# input-output_iCESDuck-ShieldControler.net
KiCad netlist of a schematic drawn in EasyEDA
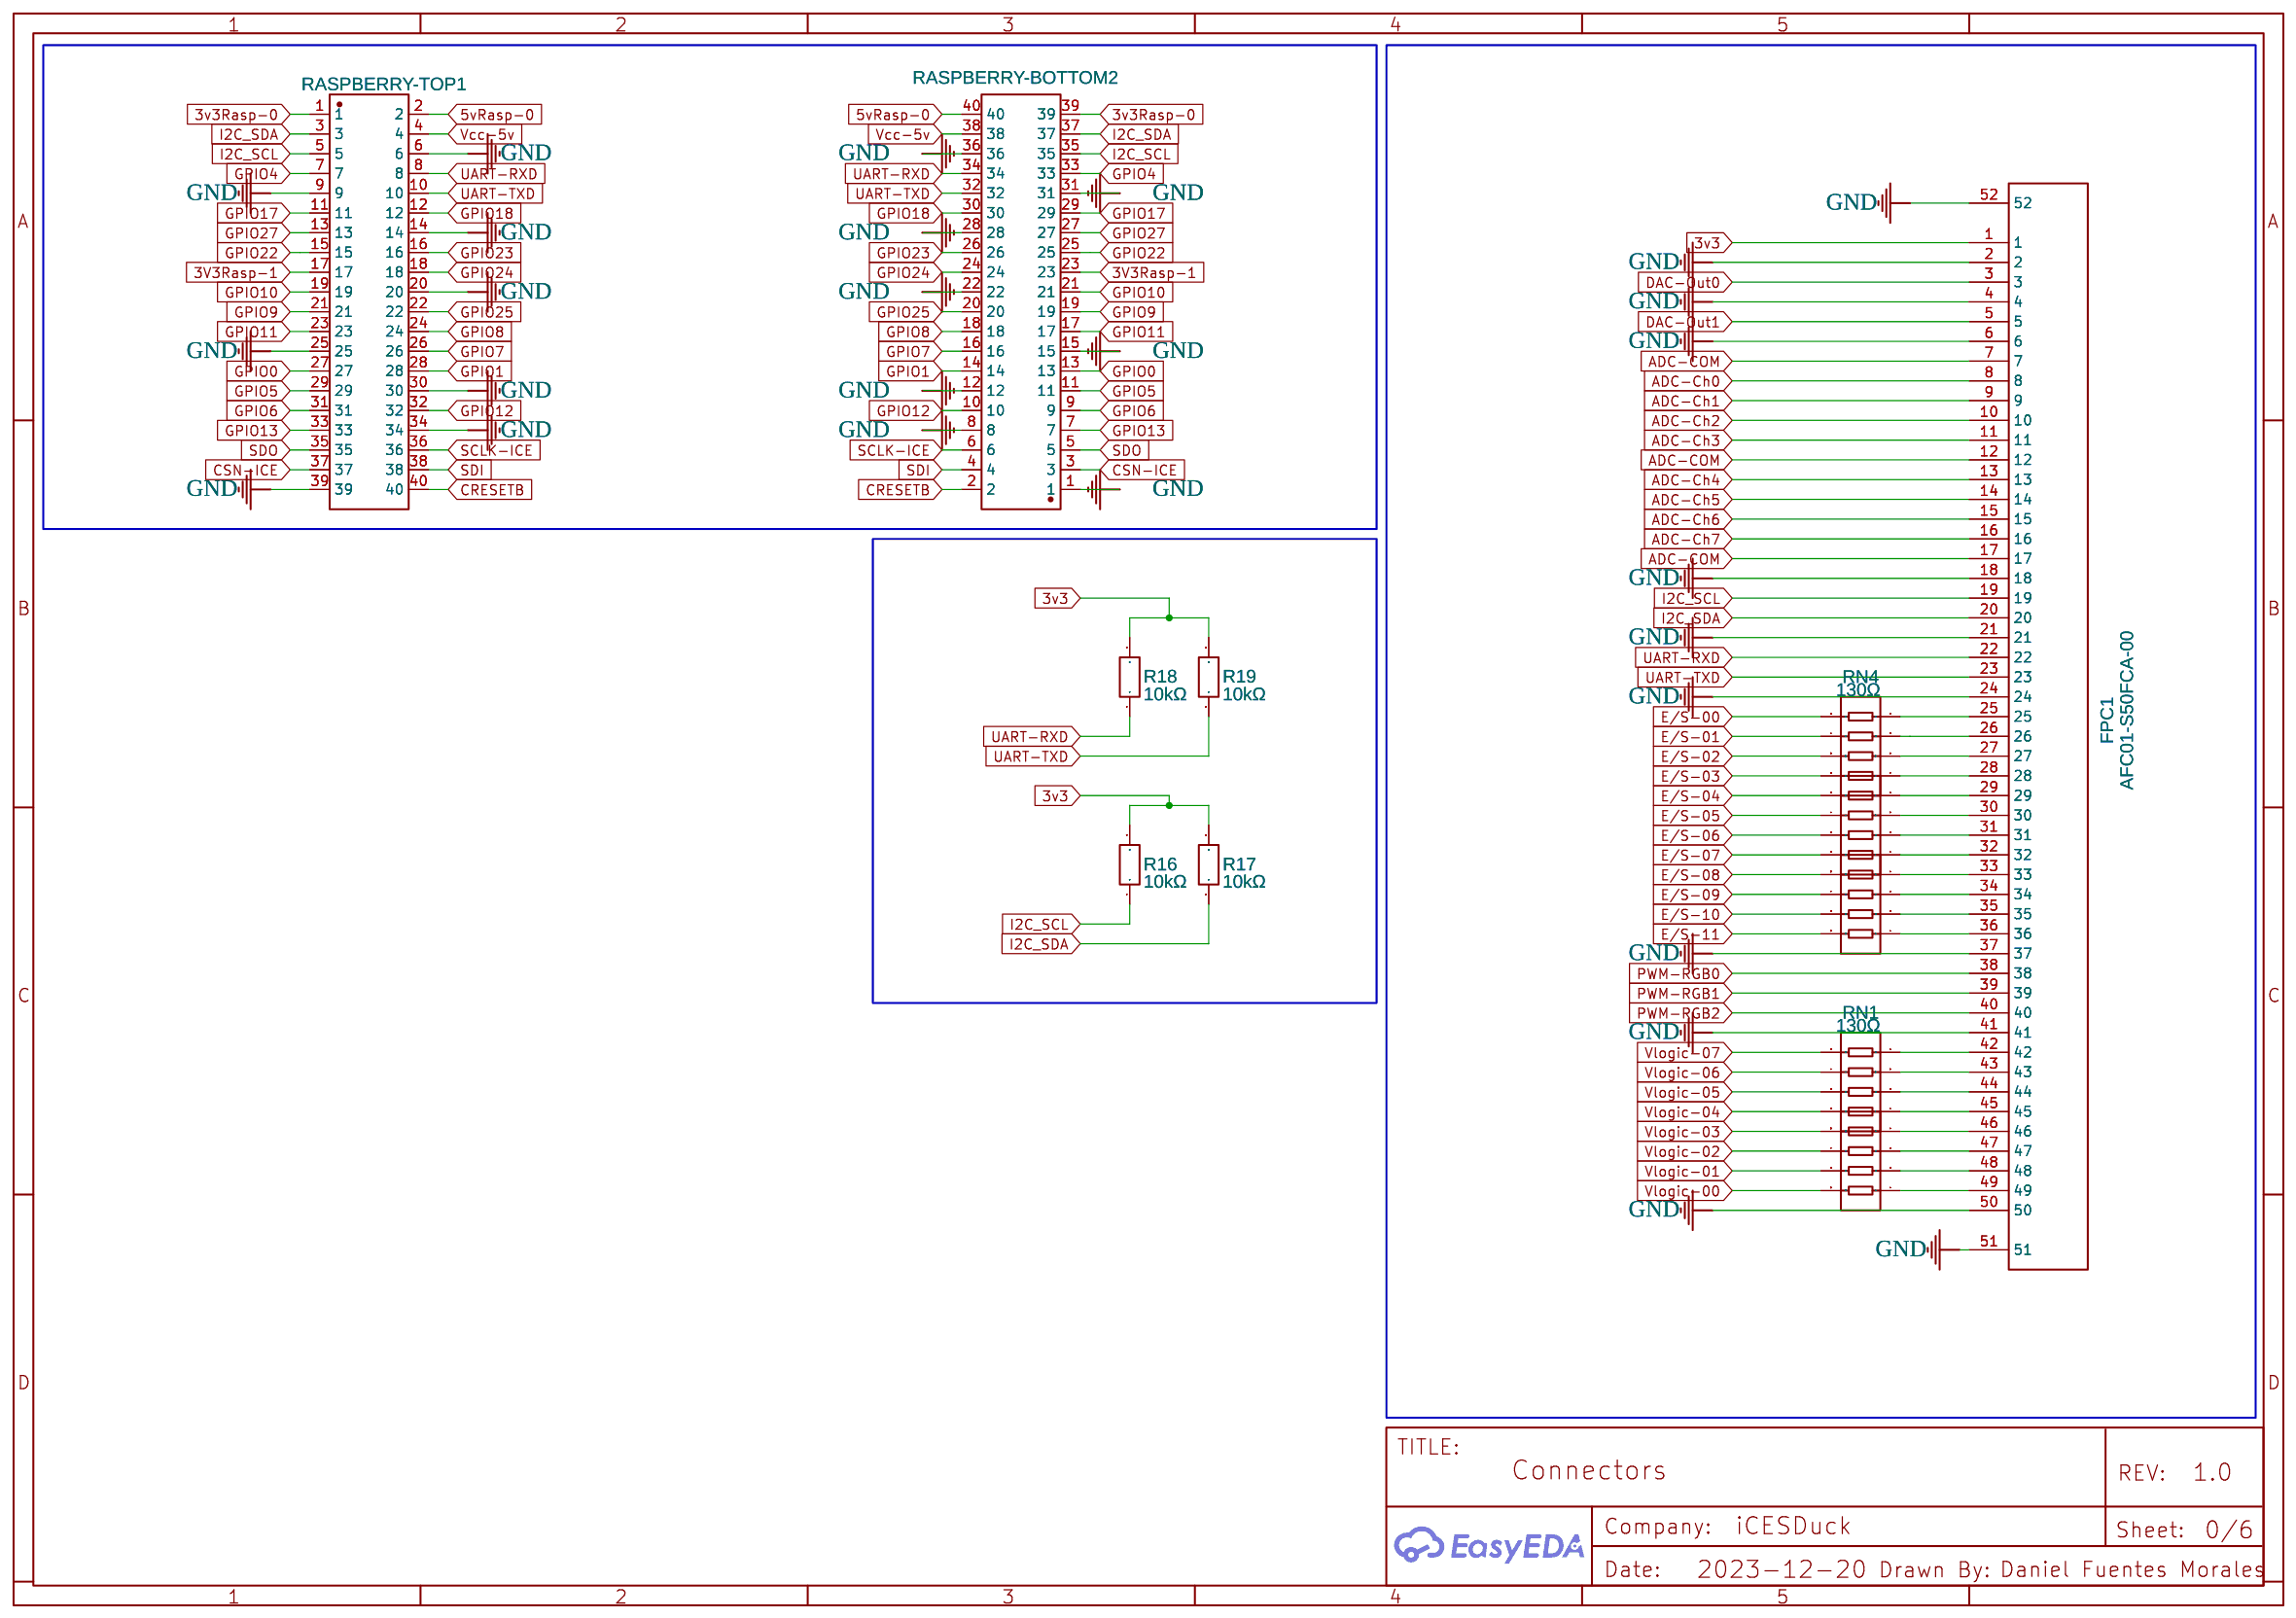
[diagram p0: Connectors]
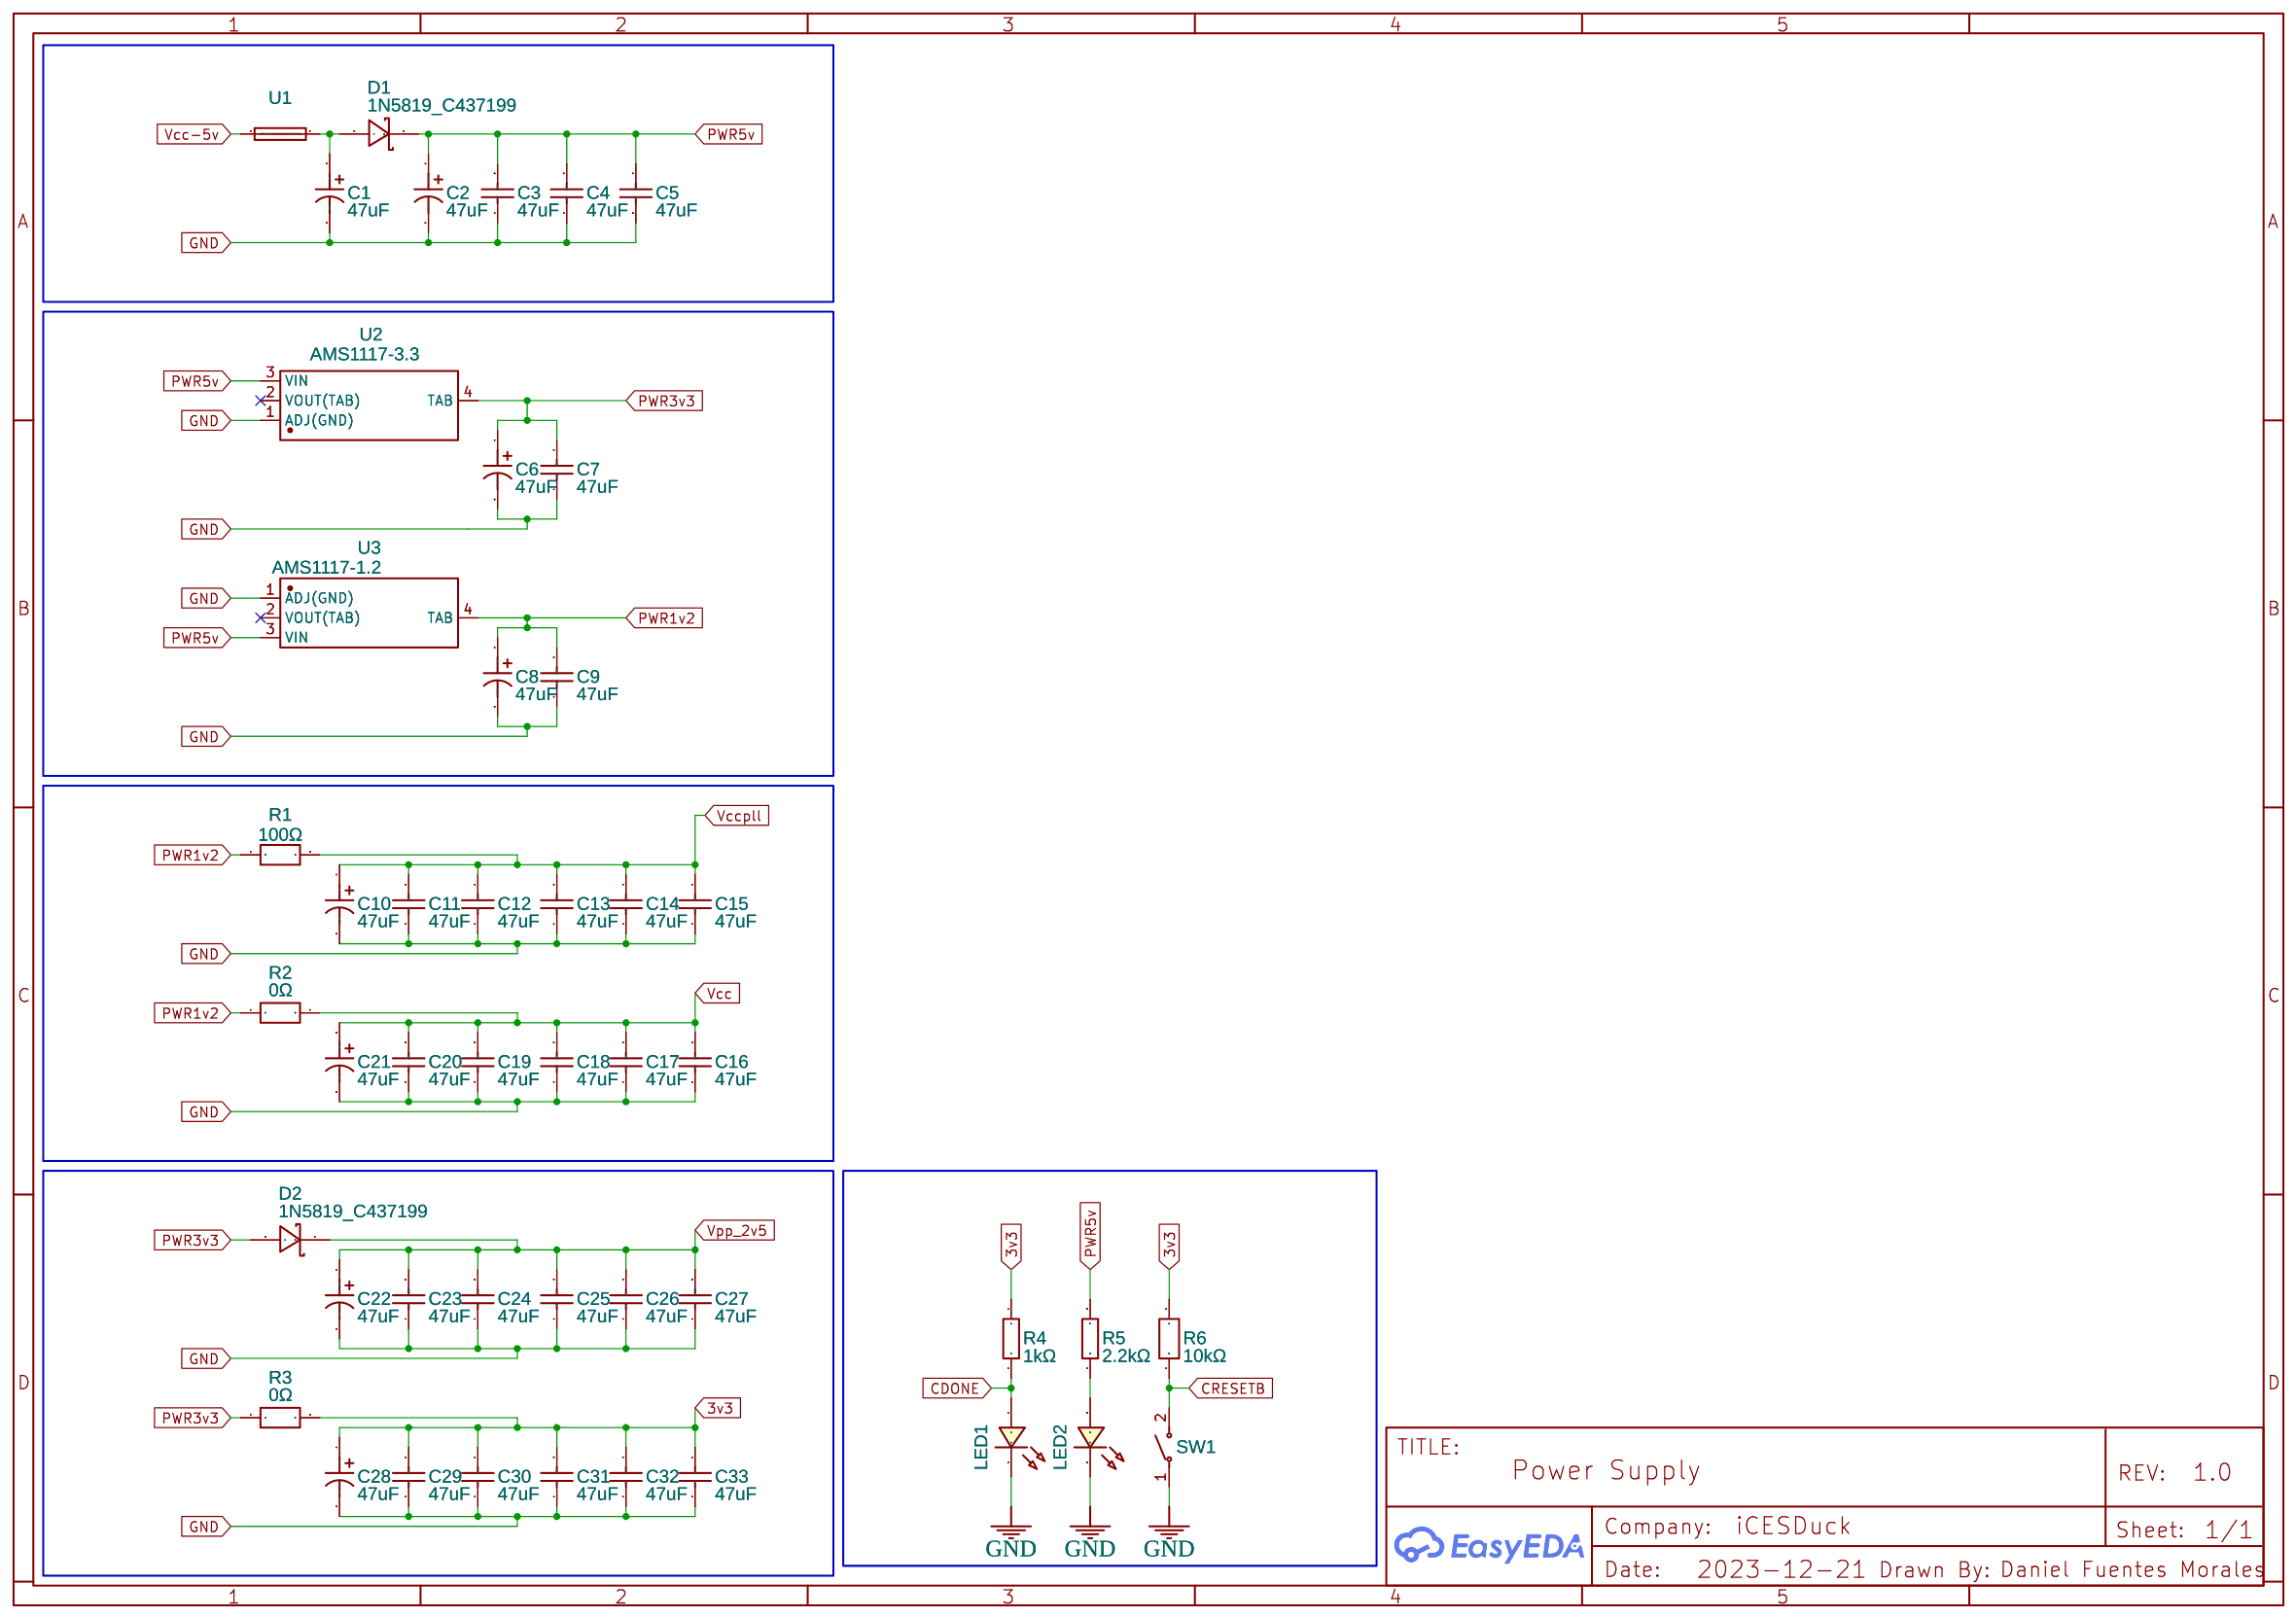
[diagram p1: power supply]
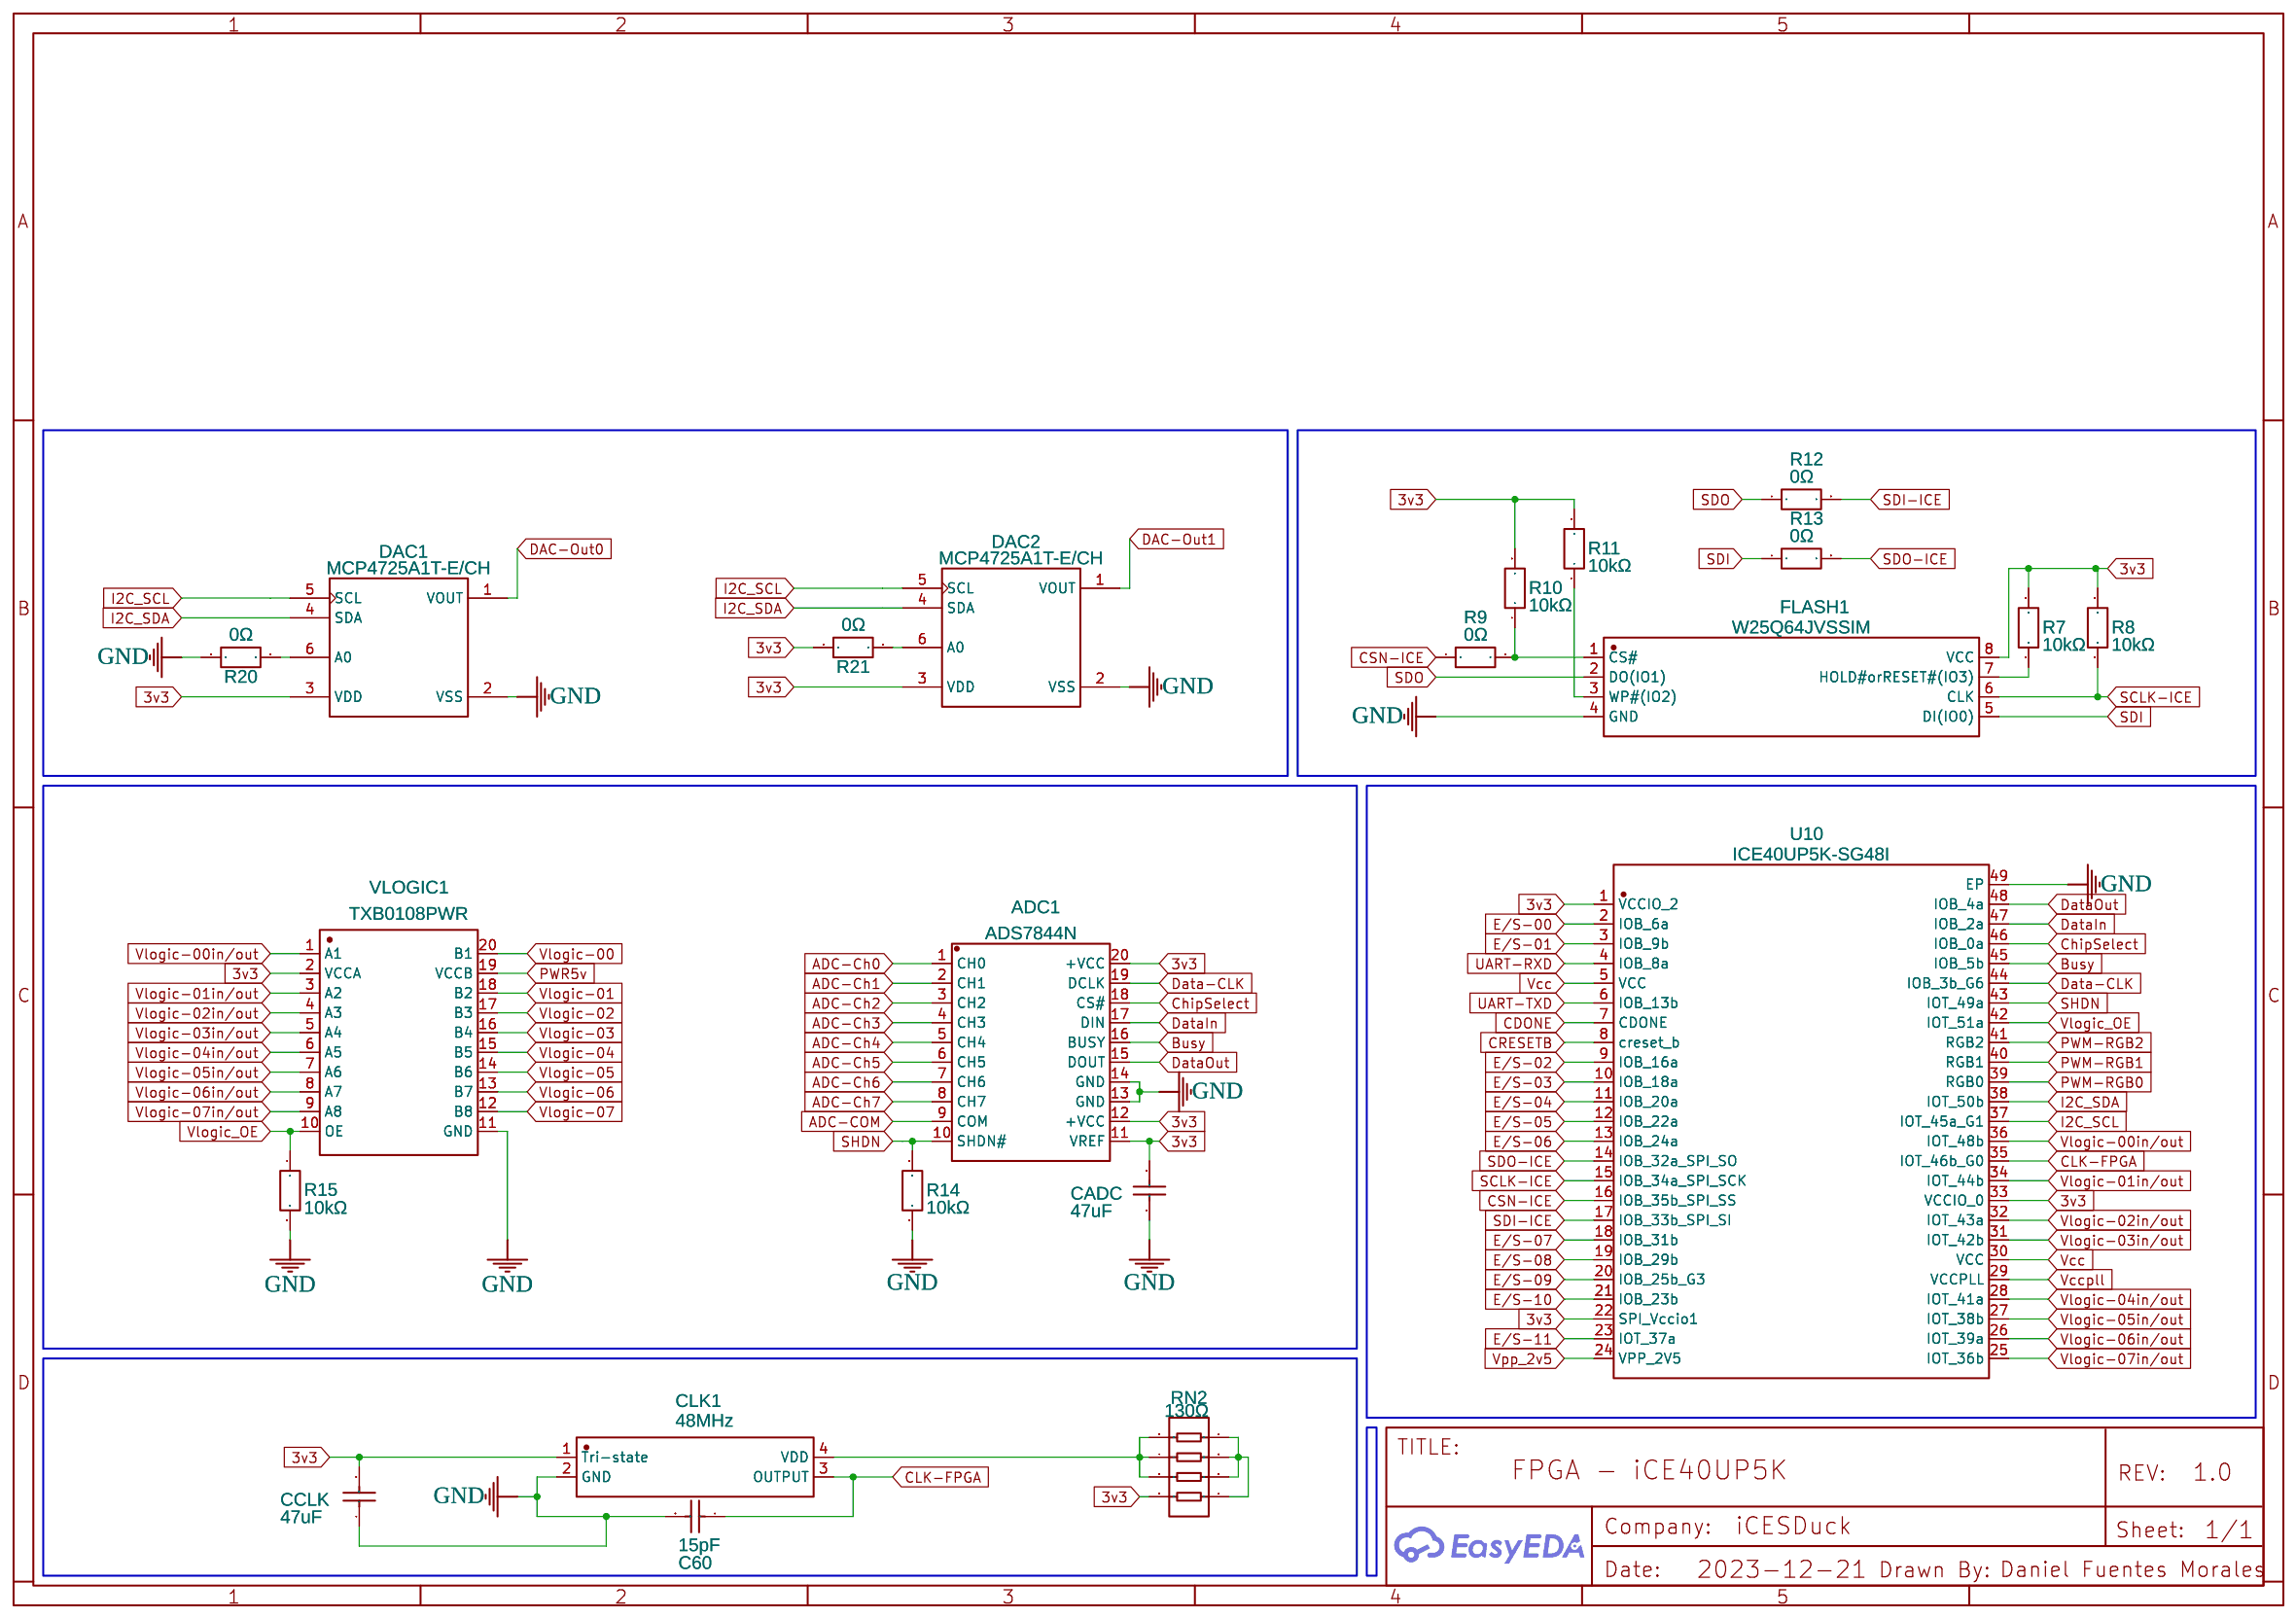
[diagram p2: FPGA - iCE40UP5k]

(export (version "E")
  (design (tool "Eeschema 10.0.6"))
  (components
    (comp (ref "FPC1")
      (value "AFC01-S50FCA-00")
      (fields (field (name "Manufacturer") "JS(钜硕电子)"))
      (libsource (lib "") (part "AFC01-S50FCA-00"))
    )
    (comp (ref "R16")
      (value "10kΩ")
      (fields (field (name "Manufacturer Part") "FRP1206J103 TS") (field (name "Manufacturer") "FOJAN(富捷)"))
      (libsource (lib "") (part "FRP1206J103 TS"))
    )
    (comp (ref "R17")
      (value "10kΩ")
      (fields (field (name "Manufacturer Part") "FRP1206J103 TS") (field (name "Manufacturer") "FOJAN(富捷)"))
      (libsource (lib "") (part "FRP1206J103 TS"))
    )
    (comp (ref "R18")
      (value "10kΩ")
      (fields (field (name "Manufacturer Part") "FRP1206J103 TS") (field (name "Manufacturer") "FOJAN(富捷)"))
      (libsource (lib "") (part "FRP1206J103 TS"))
    )
    (comp (ref "R19")
      (value "10kΩ")
      (fields (field (name "Manufacturer Part") "FRP1206J103 TS") (field (name "Manufacturer") "FOJAN(富捷)"))
      (libsource (lib "") (part "FRP1206J103 TS"))
    )
    (comp (ref "RASPBERRY-BOTTOM2")
      (value "FH-00148")
      (fields (field (name "Manufacturer") "Liansheng(连盛)"))
      (libsource (lib "") (part "FH-00148"))
    )
    (comp (ref "RASPBERRY-TOP1")
      (value "FH-00148")
      (fields (field (name "Manufacturer") "Liansheng(连盛)"))
      (libsource (lib "") (part "FH-00148_1"))
    )
    (comp (ref "RN1")
      (value "130Ω")
      (fields
        (field (name "Manufacturer Part") "4D03WGJ0131T5E")
        (field (name "Manufacturer") "UNI-ROYAL(厚声)")
      )
      (libsource (lib "") (part "4D03WGJ0131T5E"))
    )
    (comp (ref "RN3")
      (value "130Ω")
      (fields
        (field (name "Manufacturer Part") "4D03WGJ0131T5E")
        (field (name "Manufacturer") "UNI-ROYAL(厚声)")
      )
      (libsource (lib "") (part "4D03WGJ0131T5E"))
    )
    (comp (ref "RN4")
      (value "130Ω")
      (fields
        (field (name "Manufacturer Part") "4D03WGJ0131T5E")
        (field (name "Manufacturer") "UNI-ROYAL(厚声)")
      )
      (libsource (lib "") (part "4D03WGJ0131T5E"))
    )
    (comp (ref "RN5")
      (value "130Ω")
      (fields
        (field (name "Manufacturer Part") "4D03WGJ0131T5E")
        (field (name "Manufacturer") "UNI-ROYAL(厚声)")
      )
      (libsource (lib "") (part "4D03WGJ0131T5E"))
    )
    (comp (ref "RN6")
      (value "130Ω")
      (fields
        (field (name "Manufacturer Part") "4D03WGJ0131T5E")
        (field (name "Manufacturer") "UNI-ROYAL(厚声)")
      )
      (libsource (lib "") (part "4D03WGJ0131T5E"))
    )
    (comp (ref "C1")
      (value "47uF")
      (fields
        (field (name "Manufacturer Part") "CA45-A-10V-47uF-M")
        (field (name "Manufacturer") "CEC(振华新云)")
      )
      (libsource (lib "") (part "CA45-A-10V-47UF-M"))
    )
    (comp (ref "C2")
      (value "47uF")
      (fields
        (field (name "Manufacturer Part") "CA45-A-10V-47uF-M")
        (field (name "Manufacturer") "CEC(振华新云)")
      )
      (libsource (lib "") (part "CA45-A-10V-47UF-M"))
    )
    (comp (ref "C3")
      (value "47uF")
      (fields (field (name "Manufacturer Part") "C2012X5R1A476MTJ00E") (field (name "Manufacturer") "TDK"))
      (libsource (lib "") (part "C2012X5R1A476MTJ00E"))
    )
    (comp (ref "C4")
      (value "47uF")
      (fields (field (name "Manufacturer Part") "C2012X5R1A476MTJ00E") (field (name "Manufacturer") "TDK"))
      (libsource (lib "") (part "C2012X5R1A476MTJ00E"))
    )
    (comp (ref "C5")
      (value "47uF")
      (fields (field (name "Manufacturer Part") "C2012X5R1A476MTJ00E") (field (name "Manufacturer") "TDK"))
      (libsource (lib "") (part "C2012X5R1A476MTJ00E"))
    )
    (comp (ref "C6")
      (value "47uF")
      (fields
        (field (name "Manufacturer Part") "CA45-A-10V-47uF-M")
        (field (name "Manufacturer") "CEC(振华新云)")
      )
      (libsource (lib "") (part "CA45-A-10V-47UF-M"))
    )
    (comp (ref "C7")
      (value "47uF")
      (fields (field (name "Manufacturer Part") "C2012X5R1A476MTJ00E") (field (name "Manufacturer") "TDK"))
      (libsource (lib "") (part "C2012X5R1A476MTJ00E"))
    )
    (comp (ref "C8")
      (value "47uF")
      (fields
        (field (name "Manufacturer Part") "CA45-A-10V-47uF-M")
        (field (name "Manufacturer") "CEC(振华新云)")
      )
      (libsource (lib "") (part "CA45-A-10V-47UF-M"))
    )
    (comp (ref "C9")
      (value "47uF")
      (fields (field (name "Manufacturer Part") "C2012X5R1A476MTJ00E") (field (name "Manufacturer") "TDK"))
      (libsource (lib "") (part "C2012X5R1A476MTJ00E"))
    )
    (comp (ref "C10")
      (value "47uF")
      (fields
        (field (name "Manufacturer Part") "CA45-A-10V-47uF-M")
        (field (name "Manufacturer") "CEC(振华新云)")
      )
      (libsource (lib "") (part "CA45-A-10V-47UF-M"))
    )
    (comp (ref "C11")
      (value "47uF")
      (fields (field (name "Manufacturer Part") "C2012X5R1A476MTJ00E") (field (name "Manufacturer") "TDK"))
      (libsource (lib "") (part "C2012X5R1A476MTJ00E"))
    )
    (comp (ref "C12")
      (value "47uF")
      (fields (field (name "Manufacturer Part") "C2012X5R1A476MTJ00E") (field (name "Manufacturer") "TDK"))
      (libsource (lib "") (part "C2012X5R1A476MTJ00E"))
    )
    (comp (ref "C13")
      (value "47uF")
      (fields (field (name "Manufacturer Part") "C2012X5R1A476MTJ00E") (field (name "Manufacturer") "TDK"))
      (libsource (lib "") (part "C2012X5R1A476MTJ00E"))
    )
    (comp (ref "C14")
      (value "47uF")
      (fields (field (name "Manufacturer Part") "C2012X5R1A476MTJ00E") (field (name "Manufacturer") "TDK"))
      (libsource (lib "") (part "C2012X5R1A476MTJ00E"))
    )
    (comp (ref "C15")
      (value "47uF")
      (fields (field (name "Manufacturer Part") "C2012X5R1A476MTJ00E") (field (name "Manufacturer") "TDK"))
      (libsource (lib "") (part "C2012X5R1A476MTJ00E"))
    )
    (comp (ref "C16")
      (value "47uF")
      (fields (field (name "Manufacturer Part") "C2012X5R1A476MTJ00E") (field (name "Manufacturer") "TDK"))
      (libsource (lib "") (part "C2012X5R1A476MTJ00E"))
    )
    (comp (ref "C17")
      (value "47uF")
      (fields (field (name "Manufacturer Part") "C2012X5R1A476MTJ00E") (field (name "Manufacturer") "TDK"))
      (libsource (lib "") (part "C2012X5R1A476MTJ00E"))
    )
    (comp (ref "C18")
      (value "47uF")
      (fields (field (name "Manufacturer Part") "C2012X5R1A476MTJ00E") (field (name "Manufacturer") "TDK"))
      (libsource (lib "") (part "C2012X5R1A476MTJ00E"))
    )
    (comp (ref "C19")
      (value "47uF")
      (fields (field (name "Manufacturer Part") "C2012X5R1A476MTJ00E") (field (name "Manufacturer") "TDK"))
      (libsource (lib "") (part "C2012X5R1A476MTJ00E"))
    )
    (comp (ref "C20")
      (value "47uF")
      (fields (field (name "Manufacturer Part") "C2012X5R1A476MTJ00E") (field (name "Manufacturer") "TDK"))
      (libsource (lib "") (part "C2012X5R1A476MTJ00E"))
    )
    (comp (ref "C21")
      (value "47uF")
      (fields
        (field (name "Manufacturer Part") "CA45-A-10V-47uF-M")
        (field (name "Manufacturer") "CEC(振华新云)")
      )
      (libsource (lib "") (part "CA45-A-10V-47UF-M"))
    )
    (comp (ref "C22")
      (value "47uF")
      (fields
        (field (name "Manufacturer Part") "CA45-A-10V-47uF-M")
        (field (name "Manufacturer") "CEC(振华新云)")
      )
      (libsource (lib "") (part "CA45-A-10V-47UF-M"))
    )
    (comp (ref "C23")
      (value "47uF")
      (fields (field (name "Manufacturer Part") "C2012X5R1A476MTJ00E") (field (name "Manufacturer") "TDK"))
      (libsource (lib "") (part "C2012X5R1A476MTJ00E"))
    )
    (comp (ref "C24")
      (value "47uF")
      (fields (field (name "Manufacturer Part") "C2012X5R1A476MTJ00E") (field (name "Manufacturer") "TDK"))
      (libsource (lib "") (part "C2012X5R1A476MTJ00E"))
    )
    (comp (ref "C25")
      (value "47uF")
      (fields (field (name "Manufacturer Part") "C2012X5R1A476MTJ00E") (field (name "Manufacturer") "TDK"))
      (libsource (lib "") (part "C2012X5R1A476MTJ00E"))
    )
    (comp (ref "C26")
      (value "47uF")
      (fields (field (name "Manufacturer Part") "C2012X5R1A476MTJ00E") (field (name "Manufacturer") "TDK"))
      (libsource (lib "") (part "C2012X5R1A476MTJ00E"))
    )
    (comp (ref "C27")
      (value "47uF")
      (fields (field (name "Manufacturer Part") "C2012X5R1A476MTJ00E") (field (name "Manufacturer") "TDK"))
      (libsource (lib "") (part "C2012X5R1A476MTJ00E"))
    )
    (comp (ref "C28")
      (value "47uF")
      (fields
        (field (name "Manufacturer Part") "CA45-A-10V-47uF-M")
        (field (name "Manufacturer") "CEC(振华新云)")
      )
      (libsource (lib "") (part "CA45-A-10V-47UF-M"))
    )
    (comp (ref "C29")
      (value "47uF")
      (fields (field (name "Manufacturer Part") "C2012X5R1A476MTJ00E") (field (name "Manufacturer") "TDK"))
      (libsource (lib "") (part "C2012X5R1A476MTJ00E"))
    )
    (comp (ref "C30")
      (value "47uF")
      (fields (field (name "Manufacturer Part") "C2012X5R1A476MTJ00E") (field (name "Manufacturer") "TDK"))
      (libsource (lib "") (part "C2012X5R1A476MTJ00E"))
    )
    (comp (ref "C31")
      (value "47uF")
      (fields (field (name "Manufacturer Part") "C2012X5R1A476MTJ00E") (field (name "Manufacturer") "TDK"))
      (libsource (lib "") (part "C2012X5R1A476MTJ00E"))
    )
    (comp (ref "C32")
      (value "47uF")
      (fields (field (name "Manufacturer Part") "C2012X5R1A476MTJ00E") (field (name "Manufacturer") "TDK"))
      (libsource (lib "") (part "C2012X5R1A476MTJ00E"))
    )
    (comp (ref "C33")
      (value "47uF")
      (fields (field (name "Manufacturer Part") "C2012X5R1A476MTJ00E") (field (name "Manufacturer") "TDK"))
      (libsource (lib "") (part "C2012X5R1A476MTJ00E"))
    )
    (comp (ref "D1")
      (value "1N5819_C437199")
      (fields (field (name "Manufacturer Part") "1N5819") (field (name "Manufacturer") "KEXIN(科信)"))
      (libsource (lib "") (part "1N5819_C437199"))
    )
    (comp (ref "D2")
      (value "1N5819_C437199")
      (fields (field (name "Manufacturer Part") "1N5819") (field (name "Manufacturer") "KEXIN(科信)"))
      (libsource (lib "") (part "1N5819_C437199"))
    )
    (comp (ref "LED1")
      (value "LED-0603_G")
      (fields
        (field (name "Manufacturer Part") "19-217/GHC-YR1S2/3T")
        (field (name "Manufacturer") "EVERLIGHT(台湾亿光)")
      )
      (libsource (lib "") (part "LED-0603_G"))
    )
    (comp (ref "LED2")
      (value "LED-0603_G")
      (fields
        (field (name "Manufacturer Part") "19-217/GHC-YR1S2/3T")
        (field (name "Manufacturer") "EVERLIGHT(台湾亿光)")
      )
      (libsource (lib "") (part "LED-0603_G"))
    )
    (comp (ref "R1")
      (value "100Ω")
      (fields
        (field (name "Manufacturer Part") "AS05W2J0102T5E")
        (field (name "Manufacturer") "UNI-ROYAL(厚声)")
      )
      (libsource (lib "") (part "AS05W2J0102T5E"))
    )
    (comp (ref "R2")
      (value "0Ω")
      (fields
        (field (name "Manufacturer Part") "AS05W2J0102T5E")
        (field (name "Manufacturer") "UNI-ROYAL(厚声)")
      )
      (libsource (lib "") (part "AS05W2J0102T5E"))
    )
    (comp (ref "R3")
      (value "0Ω")
      (fields
        (field (name "Manufacturer Part") "AS05W2J0102T5E")
        (field (name "Manufacturer") "UNI-ROYAL(厚声)")
      )
      (libsource (lib "") (part "AS05W2J0102T5E"))
    )
    (comp (ref "R4")
      (value "1kΩ")
      (fields
        (field (name "Manufacturer Part") "0603WAF1001T5E")
        (field (name "Manufacturer") "UNI-ROYAL(厚声)")
      )
      (libsource (lib "") (part "0603WAF1001T5E"))
    )
    (comp (ref "R5")
      (value "2.2kΩ")
      (fields
        (field (name "Manufacturer Part") "0603WAF2201T5E")
        (field (name "Manufacturer") "UNI-ROYAL(厚声)")
      )
      (libsource (lib "") (part "0603WAF2201T5E"))
    )
    (comp (ref "R6")
      (value "10kΩ")
      (fields (field (name "Manufacturer Part") "FRP1206J103 TS") (field (name "Manufacturer") "FOJAN(富捷)"))
      (libsource (lib "") (part "FRP1206J103 TS"))
    )
    (comp (ref "SW1")
      (value "TS-1088R-02026")
      (fields (field (name "Manufacturer") "XUNPU(讯普)"))
      (libsource (lib "") (part "TS-1088R-02026"))
    )
    (comp (ref "U1")
      (value "0494001.NR")
      (fields (field (name "Manufacturer") "Littelfuse(美国力特)"))
      (libsource (lib "") (part "0494001.NR"))
    )
    (comp (ref "U2")
      (value "AMS1117-3.3")
      (fields (field (name "Manufacturer") "UMW(广东友台半导体)"))
      (libsource (lib "") (part "AMS1117-3.3_C347222"))
    )
    (comp (ref "U3")
      (value "AMS1117-1.2")
      (fields (field (name "Manufacturer") "UMW(广东友台半导体)"))
      (libsource (lib "") (part "AMS1117-1.2_C347218"))
    )
    (comp (ref "ADC1")
      (value "ADS7844N")
      (fields (field (name "Manufacturer") "TI(德州仪器)"))
      (libsource (lib "") (part "ADS7844N"))
    )
    (comp (ref "C60")
      (value "15pF")
      (fields
        (field (name "Manufacturer Part") "CL10C150JB8NNNC")
        (field (name "Manufacturer") "SAMSUNG(三星)")
      )
      (libsource (lib "") (part "CL10C150JB8NNNC"))
    )
    (comp (ref "CADC")
      (value "47uF")
      (fields (field (name "Manufacturer Part") "C2012X5R1A476MTJ00E") (field (name "Manufacturer") "TDK"))
      (libsource (lib "") (part "C2012X5R1A476MTJ00E"))
    )
    (comp (ref "CCLK")
      (value "47uF")
      (fields (field (name "Manufacturer Part") "C2012X5R1A476MTJ00E") (field (name "Manufacturer") "TDK"))
      (libsource (lib "") (part "C2012X5R1A476MTJ00E_1"))
    )
    (comp (ref "CLK1")
      (value "48MHz")
      (fields
        (field (name "Manufacturer Part") "S3D48.000000B20F30T")
        (field (name "Manufacturer") "SCTF(星通时频)")
      )
      (libsource (lib "") (part "S3D48.000000B20F30T"))
    )
    (comp (ref "DAC1")
      (value "MCP4725A1T-E/CH")
      (fields (field (name "Manufacturer") "MICROCHIP(美国微芯)"))
      (libsource (lib "") (part "MCP4725A1T-E/CH"))
    )
    (comp (ref "DAC2")
      (value "MCP4725A1T-E/CH")
      (fields (field (name "Manufacturer") "MICROCHIP(美国微芯)"))
      (libsource (lib "") (part "MCP4725A1T-E/CH"))
    )
    (comp (ref "FLASH1")
      (value "W25Q64JVSSIM")
      (fields (field (name "Manufacturer") "WINBOND(华邦)"))
      (libsource (lib "") (part "W25Q64JVSSIM"))
    )
    (comp (ref "R7")
      (value "10kΩ")
      (fields (field (name "Manufacturer Part") "FRP1206J103 TS") (field (name "Manufacturer") "FOJAN(富捷)"))
      (libsource (lib "") (part "FRP1206J103 TS"))
    )
    (comp (ref "R8")
      (value "10kΩ")
      (fields (field (name "Manufacturer Part") "FRP1206J103 TS") (field (name "Manufacturer") "FOJAN(富捷)"))
      (libsource (lib "") (part "FRP1206J103 TS"))
    )
    (comp (ref "R9")
      (value "0Ω")
      (fields
        (field (name "Manufacturer Part") "AS05W2J0102T5E")
        (field (name "Manufacturer") "UNI-ROYAL(厚声)")
      )
      (libsource (lib "") (part "AS05W2J0102T5E"))
    )
    (comp (ref "R10")
      (value "10kΩ")
      (fields (field (name "Manufacturer Part") "FRP1206J103 TS") (field (name "Manufacturer") "FOJAN(富捷)"))
      (libsource (lib "") (part "FRP1206J103 TS"))
    )
    (comp (ref "R11")
      (value "10kΩ")
      (fields (field (name "Manufacturer Part") "FRP1206J103 TS") (field (name "Manufacturer") "FOJAN(富捷)"))
      (libsource (lib "") (part "FRP1206J103 TS"))
    )
    (comp (ref "R12")
      (value "0Ω")
      (fields
        (field (name "Manufacturer Part") "AS05W2J0102T5E")
        (field (name "Manufacturer") "UNI-ROYAL(厚声)")
      )
      (libsource (lib "") (part "AS05W2J0102T5E"))
    )
    (comp (ref "R13")
      (value "0Ω")
      (fields
        (field (name "Manufacturer Part") "AS05W2J0102T5E")
        (field (name "Manufacturer") "UNI-ROYAL(厚声)")
      )
      (libsource (lib "") (part "AS05W2J0102T5E"))
    )
    (comp (ref "R14")
      (value "10kΩ")
      (fields (field (name "Manufacturer Part") "FRP1206J103 TS") (field (name "Manufacturer") "FOJAN(富捷)"))
      (libsource (lib "") (part "FRP1206J103 TS"))
    )
    (comp (ref "R15")
      (value "10kΩ")
      (fields (field (name "Manufacturer Part") "FRP1206J103 TS") (field (name "Manufacturer") "FOJAN(富捷)"))
      (libsource (lib "") (part "FRP1206J103 TS_1"))
    )
    (comp (ref "R20")
      (value "0Ω")
      (fields
        (field (name "Manufacturer Part") "AS05W2J0102T5E")
        (field (name "Manufacturer") "UNI-ROYAL(厚声)")
      )
      (libsource (lib "") (part "AS05W2J0102T5E"))
    )
    (comp (ref "R21")
      (value "0Ω")
      (fields
        (field (name "Manufacturer Part") "AS05W2J0102T5E")
        (field (name "Manufacturer") "UNI-ROYAL(厚声)")
      )
      (libsource (lib "") (part "AS05W2J0102T5E"))
    )
    (comp (ref "RN2")
      (value "130Ω")
      (fields
        (field (name "Manufacturer Part") "4D03WGJ0131T5E")
        (field (name "Manufacturer") "UNI-ROYAL(厚声)")
      )
      (libsource (lib "") (part "4D03WGJ0131T5E"))
    )
    (comp (ref "U10")
      (value "ICE40UP5K-SG48I")
      (fields (field (name "Manufacturer") "LATTICE(莱迪思)"))
      (libsource (lib "") (part "ICE40UP5K-SG48I"))
    )
    (comp (ref "VLOGIC1")
      (value "TXB0108PWR")
      (fields (field (name "Manufacturer") "TI(德州仪器)"))
      (libsource (lib "") (part "TXB0108PWR"))
    )
  )
  (nets
    (net (code "1") (name "3V3Rasp-1") (class "Default")
      (node (ref "RASPBERRY-BOTTOM2") (pin "23") (pinfunction "23_23") (pintype "unspecified"))
      (node (ref "RASPBERRY-TOP1") (pin "17") (pinfunction "17_17") (pintype "unspecified"))
    )
    (net (code "2") (name "3v3") (class "Default")
      (node (ref "ADC1") (pin "11") (pinfunction "VREF_11") (pintype "unspecified"))
      (node (ref "ADC1") (pin "12") (pinfunction "+VCC_12") (pintype "unspecified"))
      (node (ref "ADC1") (pin "20") (pinfunction "+VCC_20") (pintype "unspecified"))
      (node (ref "C28") (pin "1") (pinfunction "1_1") (pintype "input"))
      (node (ref "C29") (pin "2") (pinfunction "2_2") (pintype "input"))
      (node (ref "C30") (pin "2") (pinfunction "2_2") (pintype "input"))
      (node (ref "C31") (pin "2") (pinfunction "2_2") (pintype "input"))
      (node (ref "C32") (pin "2") (pinfunction "2_2") (pintype "input"))
      (node (ref "C33") (pin "2") (pinfunction "2_2") (pintype "input"))
      (node (ref "CADC") (pin "2") (pinfunction "2_2") (pintype "input"))
      (node (ref "CCLK") (pin "2") (pinfunction "2_2") (pintype "input"))
      (node (ref "CLK1") (pin "1") (pinfunction "Tri-state_1") (pintype "unspecified"))
      (node (ref "DAC1") (pin "3") (pinfunction "VDD_3") (pintype "passive"))
      (node (ref "DAC2") (pin "3") (pinfunction "VDD_3") (pintype "passive"))
      (node (ref "FLASH1") (pin "8") (pinfunction "VCC_8") (pintype "unspecified"))
      (node (ref "FPC1") (pin "1") (pinfunction "1_1") (pintype "unspecified"))
      (node (ref "R10") (pin "2") (pinfunction "2_2") (pintype "unspecified"))
      (node (ref "R11") (pin "2") (pinfunction "2_2") (pintype "unspecified"))
      (node (ref "R16") (pin "2") (pinfunction "2_2") (pintype "unspecified"))
      (node (ref "R17") (pin "2") (pinfunction "2_2") (pintype "unspecified"))
      (node (ref "R18") (pin "2") (pinfunction "2_2") (pintype "unspecified"))
      (node (ref "R19") (pin "2") (pinfunction "2_2") (pintype "unspecified"))
      (node (ref "R21") (pin "1") (pinfunction "1_1") (pintype "unspecified"))
      (node (ref "R3") (pin "2") (pinfunction "2_2") (pintype "unspecified"))
      (node (ref "R4") (pin "2") (pinfunction "2_2") (pintype "input"))
      (node (ref "R6") (pin "2") (pinfunction "2_2") (pintype "unspecified"))
      (node (ref "R7") (pin "2") (pinfunction "2_2") (pintype "unspecified"))
      (node (ref "R8") (pin "2") (pinfunction "2_2") (pintype "unspecified"))
      (node (ref "RN2") (pin "5") (pinfunction "5_5") (pintype "unspecified"))
      (node (ref "U10") (pin "1") (pinfunction "VCCIO_2_1") (pintype "unspecified"))
      (node (ref "U10") (pin "22") (pinfunction "SPI_Vccio1_22") (pintype "unspecified"))
      (node (ref "U10") (pin "33") (pinfunction "VCCIO_0_33") (pintype "unspecified"))
      (node (ref "VLOGIC1") (pin "2") (pinfunction "VCCA_2") (pintype "unspecified"))
    )
    (net (code "3") (name "3v3Rasp-0") (class "Default")
      (node (ref "RASPBERRY-BOTTOM2") (pin "39") (pinfunction "39_39") (pintype "unspecified"))
      (node (ref "RASPBERRY-TOP1") (pin "1") (pinfunction "1_1") (pintype "unspecified"))
    )
    (net (code "4") (name "5vRasp-0") (class "Default")
      (node (ref "RASPBERRY-BOTTOM2") (pin "40") (pinfunction "40_40") (pintype "unspecified"))
      (node (ref "RASPBERRY-TOP1") (pin "2") (pinfunction "2_2") (pintype "unspecified"))
    )
    (net (code "5") (name "ADC-COM") (class "Default")
      (node (ref "ADC1") (pin "9") (pinfunction "COM_9") (pintype "unspecified"))
      (node (ref "FPC1") (pin "12") (pinfunction "12_12") (pintype "unspecified"))
      (node (ref "FPC1") (pin "17") (pinfunction "17_17") (pintype "unspecified"))
      (node (ref "FPC1") (pin "7") (pinfunction "7_7") (pintype "unspecified"))
    )
    (net (code "6") (name "ADC-Ch0") (class "Default")
      (node (ref "ADC1") (pin "1") (pinfunction "CH0_1") (pintype "unspecified"))
      (node (ref "FPC1") (pin "8") (pinfunction "8_8") (pintype "unspecified"))
    )
    (net (code "7") (name "ADC-Ch1") (class "Default")
      (node (ref "ADC1") (pin "2") (pinfunction "CH1_2") (pintype "unspecified"))
      (node (ref "FPC1") (pin "9") (pinfunction "9_9") (pintype "unspecified"))
    )
    (net (code "8") (name "ADC-Ch2") (class "Default")
      (node (ref "ADC1") (pin "3") (pinfunction "CH2_3") (pintype "unspecified"))
      (node (ref "FPC1") (pin "10") (pinfunction "10_10") (pintype "unspecified"))
    )
    (net (code "9") (name "ADC-Ch3") (class "Default")
      (node (ref "ADC1") (pin "4") (pinfunction "CH3_4") (pintype "unspecified"))
      (node (ref "FPC1") (pin "11") (pinfunction "11_11") (pintype "unspecified"))
    )
    (net (code "10") (name "ADC-Ch4") (class "Default")
      (node (ref "ADC1") (pin "5") (pinfunction "CH4_5") (pintype "unspecified"))
      (node (ref "FPC1") (pin "13") (pinfunction "13_13") (pintype "unspecified"))
    )
    (net (code "11") (name "ADC-Ch5") (class "Default")
      (node (ref "ADC1") (pin "6") (pinfunction "CH5_6") (pintype "unspecified"))
      (node (ref "FPC1") (pin "14") (pinfunction "14_14") (pintype "unspecified"))
    )
    (net (code "12") (name "ADC-Ch6") (class "Default")
      (node (ref "ADC1") (pin "7") (pinfunction "CH6_7") (pintype "unspecified"))
      (node (ref "FPC1") (pin "15") (pinfunction "15_15") (pintype "unspecified"))
    )
    (net (code "13") (name "ADC-Ch7") (class "Default")
      (node (ref "ADC1") (pin "8") (pinfunction "CH7_8") (pintype "unspecified"))
      (node (ref "FPC1") (pin "16") (pinfunction "16_16") (pintype "unspecified"))
    )
    (net (code "14") (name "Busy") (class "Default")
      (node (ref "ADC1") (pin "16") (pinfunction "BUSY_16") (pintype "unspecified"))
      (node (ref "U10") (pin "45") (pinfunction "IOB_5b_45") (pintype "unspecified"))
    )
    (net (code "15") (name "CDONE") (class "Default")
      (node (ref "LED1") (pin "1") (pinfunction "1_1") (pintype "unspecified"))
      (node (ref "R4") (pin "1") (pinfunction "1_1") (pintype "input"))
      (node (ref "U10") (pin "7") (pinfunction "CDONE_7") (pintype "unspecified"))
    )
    (net (code "16") (name "CLK-FPGA") (class "Default")
      (node (ref "C60") (pin "1") (pinfunction "1_1") (pintype "input"))
      (node (ref "CLK1") (pin "3") (pinfunction "OUTPUT_3") (pintype "unspecified"))
      (node (ref "U10") (pin "35") (pinfunction "IOT_46b_G0_35") (pintype "unspecified"))
    )
    (net (code "17") (name "CRESETB") (class "Default")
      (node (ref "R6") (pin "1") (pinfunction "1_1") (pintype "unspecified"))
      (node (ref "RASPBERRY-BOTTOM2") (pin "2") (pinfunction "2_2") (pintype "unspecified"))
      (node (ref "RASPBERRY-TOP1") (pin "40") (pinfunction "40_40") (pintype "unspecified"))
      (node (ref "SW1") (pin "2") (pinfunction "2_2") (pintype "unspecified"))
      (node (ref "U10") (pin "8") (pinfunction "creset_b_8") (pintype "unspecified"))
    )
    (net (code "18") (name "CSN-ICE") (class "Default")
      (node (ref "R9") (pin "1") (pinfunction "1_1") (pintype "unspecified"))
      (node (ref "RASPBERRY-BOTTOM2") (pin "3") (pinfunction "3_3") (pintype "unspecified"))
      (node (ref "RASPBERRY-TOP1") (pin "37") (pinfunction "37_37") (pintype "unspecified"))
      (node (ref "U10") (pin "16") (pinfunction "IOB_35b_SPI_SS_16") (pintype "unspecified"))
    )
    (net (code "19") (name "ChipSelect") (class "Default")
      (node (ref "ADC1") (pin "18") (pinfunction "CS#_18") (pintype "unspecified"))
      (node (ref "U10") (pin "46") (pinfunction "IOB_0a_46") (pintype "unspecified"))
    )
    (net (code "20") (name "DAC-Out0") (class "Default")
      (node (ref "DAC1") (pin "1") (pinfunction "VOUT_1") (pintype "output"))
      (node (ref "FPC1") (pin "3") (pinfunction "3_3") (pintype "unspecified"))
    )
    (net (code "21") (name "DAC-Out1") (class "Default")
      (node (ref "DAC2") (pin "1") (pinfunction "VOUT_1") (pintype "output"))
      (node (ref "FPC1") (pin "5") (pinfunction "5_5") (pintype "unspecified"))
    )
    (net (code "22") (name "Data-CLK") (class "Default")
      (node (ref "ADC1") (pin "19") (pinfunction "DCLK_19") (pintype "unspecified"))
      (node (ref "U10") (pin "44") (pinfunction "IOB_3b_G6_44") (pintype "unspecified"))
    )
    (net (code "23") (name "DataIn") (class "Default")
      (node (ref "ADC1") (pin "17") (pinfunction "DIN_17") (pintype "unspecified"))
      (node (ref "U10") (pin "47") (pinfunction "IOB_2a_47") (pintype "unspecified"))
    )
    (net (code "24") (name "DataOut") (class "Default")
      (node (ref "ADC1") (pin "15") (pinfunction "DOUT_15") (pintype "unspecified"))
      (node (ref "U10") (pin "48") (pinfunction "IOB_4a_48") (pintype "unspecified"))
    )
    (net (code "25") (name "E{slash}S-00") (class "Default")
      (node (ref "RN4") (pin "8") (pinfunction "8_8") (pintype "unspecified"))
      (node (ref "U10") (pin "2") (pinfunction "IOB_6a_2") (pintype "unspecified"))
    )
    (net (code "26") (name "E{slash}S-01") (class "Default")
      (node (ref "RN4") (pin "7") (pinfunction "7_7") (pintype "unspecified"))
      (node (ref "U10") (pin "3") (pinfunction "IOB_9b_3") (pintype "unspecified"))
    )
    (net (code "27") (name "E{slash}S-02") (class "Default")
      (node (ref "RN4") (pin "6") (pinfunction "6_6") (pintype "unspecified"))
      (node (ref "U10") (pin "9") (pinfunction "IOB_16a_9") (pintype "unspecified"))
    )
    (net (code "28") (name "E{slash}S-03") (class "Default")
      (node (ref "RN4") (pin "5") (pinfunction "5_5") (pintype "unspecified"))
      (node (ref "U10") (pin "10") (pinfunction "IOB_18a_10") (pintype "unspecified"))
    )
    (net (code "29") (name "E{slash}S-04") (class "Default")
      (node (ref "RN5") (pin "8") (pinfunction "8_8") (pintype "unspecified"))
      (node (ref "U10") (pin "11") (pinfunction "IOB_20a_11") (pintype "unspecified"))
    )
    (net (code "30") (name "E{slash}S-05") (class "Default")
      (node (ref "RN5") (pin "7") (pinfunction "7_7") (pintype "unspecified"))
      (node (ref "U10") (pin "12") (pinfunction "IOB_22a_12") (pintype "unspecified"))
    )
    (net (code "31") (name "E{slash}S-06") (class "Default")
      (node (ref "RN5") (pin "6") (pinfunction "6_6") (pintype "unspecified"))
      (node (ref "U10") (pin "13") (pinfunction "IOB_24a_13") (pintype "unspecified"))
    )
    (net (code "32") (name "E{slash}S-07") (class "Default")
      (node (ref "RN5") (pin "5") (pinfunction "5_5") (pintype "unspecified"))
      (node (ref "U10") (pin "18") (pinfunction "IOB_31b_18") (pintype "unspecified"))
    )
    (net (code "33") (name "E{slash}S-08") (class "Default")
      (node (ref "RN6") (pin "8") (pinfunction "8_8") (pintype "unspecified"))
      (node (ref "U10") (pin "19") (pinfunction "IOB_29b_19") (pintype "unspecified"))
    )
    (net (code "34") (name "E{slash}S-09") (class "Default")
      (node (ref "RN6") (pin "7") (pinfunction "7_7") (pintype "unspecified"))
      (node (ref "U10") (pin "20") (pinfunction "IOB_25b_G3_20") (pintype "unspecified"))
    )
    (net (code "35") (name "E{slash}S-10") (class "Default")
      (node (ref "RN6") (pin "6") (pinfunction "6_6") (pintype "unspecified"))
      (node (ref "U10") (pin "21") (pinfunction "IOB_23b_21") (pintype "unspecified"))
    )
    (net (code "36") (name "E{slash}S-11") (class "Default")
      (node (ref "RN6") (pin "5") (pinfunction "5_5") (pintype "unspecified"))
      (node (ref "U10") (pin "23") (pinfunction "IOT_37a_23") (pintype "unspecified"))
    )
    (net (code "37") (name "GND") (class "Default")
      (node (ref "ADC1") (pin "13") (pinfunction "GND_13") (pintype "unspecified"))
      (node (ref "ADC1") (pin "14") (pinfunction "GND_14") (pintype "unspecified"))
      (node (ref "C1") (pin "2") (pinfunction "2_2") (pintype "input"))
      (node (ref "C10") (pin "2") (pinfunction "2_2") (pintype "input"))
      (node (ref "C11") (pin "1") (pinfunction "1_1") (pintype "input"))
      (node (ref "C12") (pin "1") (pinfunction "1_1") (pintype "input"))
      (node (ref "C13") (pin "1") (pinfunction "1_1") (pintype "input"))
      (node (ref "C14") (pin "1") (pinfunction "1_1") (pintype "input"))
      (node (ref "C15") (pin "1") (pinfunction "1_1") (pintype "input"))
      (node (ref "C16") (pin "1") (pinfunction "1_1") (pintype "input"))
      (node (ref "C17") (pin "1") (pinfunction "1_1") (pintype "input"))
      (node (ref "C18") (pin "1") (pinfunction "1_1") (pintype "input"))
      (node (ref "C19") (pin "1") (pinfunction "1_1") (pintype "input"))
      (node (ref "C2") (pin "2") (pinfunction "2_2") (pintype "input"))
      (node (ref "C20") (pin "1") (pinfunction "1_1") (pintype "input"))
      (node (ref "C21") (pin "2") (pinfunction "2_2") (pintype "input"))
      (node (ref "C22") (pin "2") (pinfunction "2_2") (pintype "input"))
      (node (ref "C23") (pin "1") (pinfunction "1_1") (pintype "input"))
      (node (ref "C24") (pin "1") (pinfunction "1_1") (pintype "input"))
      (node (ref "C25") (pin "1") (pinfunction "1_1") (pintype "input"))
      (node (ref "C26") (pin "1") (pinfunction "1_1") (pintype "input"))
      (node (ref "C27") (pin "1") (pinfunction "1_1") (pintype "input"))
      (node (ref "C28") (pin "2") (pinfunction "2_2") (pintype "input"))
      (node (ref "C29") (pin "1") (pinfunction "1_1") (pintype "input"))
      (node (ref "C3") (pin "1") (pinfunction "1_1") (pintype "input"))
      (node (ref "C30") (pin "1") (pinfunction "1_1") (pintype "input"))
      (node (ref "C31") (pin "1") (pinfunction "1_1") (pintype "input"))
      (node (ref "C32") (pin "1") (pinfunction "1_1") (pintype "input"))
      (node (ref "C33") (pin "1") (pinfunction "1_1") (pintype "input"))
      (node (ref "C4") (pin "1") (pinfunction "1_1") (pintype "input"))
      (node (ref "C5") (pin "1") (pinfunction "1_1") (pintype "input"))
      (node (ref "C6") (pin "2") (pinfunction "2_2") (pintype "input"))
      (node (ref "C60") (pin "2") (pinfunction "2_2") (pintype "input"))
      (node (ref "C7") (pin "1") (pinfunction "1_1") (pintype "input"))
      (node (ref "C8") (pin "2") (pinfunction "2_2") (pintype "input"))
      (node (ref "C9") (pin "1") (pinfunction "1_1") (pintype "input"))
      (node (ref "CADC") (pin "1") (pinfunction "1_1") (pintype "input"))
      (node (ref "CCLK") (pin "1") (pinfunction "1_1") (pintype "input"))
      (node (ref "CLK1") (pin "2") (pinfunction "GND_2") (pintype "unspecified"))
      (node (ref "DAC1") (pin "2") (pinfunction "VSS_2") (pintype "passive"))
      (node (ref "DAC2") (pin "2") (pinfunction "VSS_2") (pintype "passive"))
      (node (ref "FLASH1") (pin "4") (pinfunction "GND_4") (pintype "unspecified"))
      (node (ref "FPC1") (pin "18") (pinfunction "18_18") (pintype "unspecified"))
      (node (ref "FPC1") (pin "2") (pinfunction "2_2") (pintype "unspecified"))
      (node (ref "FPC1") (pin "21") (pinfunction "21_21") (pintype "unspecified"))
      (node (ref "FPC1") (pin "24") (pinfunction "24_24") (pintype "unspecified"))
      (node (ref "FPC1") (pin "37") (pinfunction "37_37") (pintype "unspecified"))
      (node (ref "FPC1") (pin "4") (pinfunction "4_4") (pintype "unspecified"))
      (node (ref "FPC1") (pin "41") (pinfunction "41_41") (pintype "unspecified"))
      (node (ref "FPC1") (pin "50") (pinfunction "50_50") (pintype "unspecified"))
      (node (ref "FPC1") (pin "51") (pinfunction "51_51") (pintype "unspecified"))
      (node (ref "FPC1") (pin "52") (pinfunction "52_52") (pintype "unspecified"))
      (node (ref "FPC1") (pin "6") (pinfunction "6_6") (pintype "unspecified"))
      (node (ref "LED1") (pin "2") (pinfunction "2_2") (pintype "unspecified"))
      (node (ref "LED2") (pin "2") (pinfunction "2_2") (pintype "unspecified"))
      (node (ref "R14") (pin "1") (pinfunction "1_1") (pintype "unspecified"))
      (node (ref "R15") (pin "2") (pinfunction "2_2") (pintype "unspecified"))
      (node (ref "R20") (pin "1") (pinfunction "1_1") (pintype "unspecified"))
      (node (ref "RASPBERRY-BOTTOM2") (pin "1") (pinfunction "1_1") (pintype "unspecified"))
      (node (ref "RASPBERRY-BOTTOM2") (pin "12") (pinfunction "12_12") (pintype "unspecified"))
      (node (ref "RASPBERRY-BOTTOM2") (pin "15") (pinfunction "15_15") (pintype "unspecified"))
      (node (ref "RASPBERRY-BOTTOM2") (pin "22") (pinfunction "22_22") (pintype "unspecified"))
      (node (ref "RASPBERRY-BOTTOM2") (pin "28") (pinfunction "28_28") (pintype "unspecified"))
      (node (ref "RASPBERRY-BOTTOM2") (pin "31") (pinfunction "31_31") (pintype "unspecified"))
      (node (ref "RASPBERRY-BOTTOM2") (pin "36") (pinfunction "36_36") (pintype "unspecified"))
      (node (ref "RASPBERRY-BOTTOM2") (pin "8") (pinfunction "8_8") (pintype "unspecified"))
      (node (ref "RASPBERRY-TOP1") (pin "14") (pinfunction "14_14") (pintype "unspecified"))
      (node (ref "RASPBERRY-TOP1") (pin "20") (pinfunction "20_20") (pintype "unspecified"))
      (node (ref "RASPBERRY-TOP1") (pin "25") (pinfunction "25_25") (pintype "unspecified"))
      (node (ref "RASPBERRY-TOP1") (pin "30") (pinfunction "30_30") (pintype "unspecified"))
      (node (ref "RASPBERRY-TOP1") (pin "34") (pinfunction "34_34") (pintype "unspecified"))
      (node (ref "RASPBERRY-TOP1") (pin "39") (pinfunction "39_39") (pintype "unspecified"))
      (node (ref "RASPBERRY-TOP1") (pin "6") (pinfunction "6_6") (pintype "unspecified"))
      (node (ref "RASPBERRY-TOP1") (pin "9") (pinfunction "9_9") (pintype "unspecified"))
      (node (ref "SW1") (pin "1") (pinfunction "1_1") (pintype "unspecified"))
      (node (ref "U10") (pin "49") (pinfunction "EP_49") (pintype "unspecified"))
      (node (ref "U2") (pin "1") (pinfunction "ADJ(GND)_1") (pintype "unspecified"))
      (node (ref "U3") (pin "1") (pinfunction "ADJ(GND)_1") (pintype "unspecified"))
      (node (ref "VLOGIC1") (pin "11") (pinfunction "GND_11") (pintype "unspecified"))
    )
    (net (code "38") (name "GPIO0") (class "Default")
      (node (ref "RASPBERRY-BOTTOM2") (pin "13") (pinfunction "13_13") (pintype "unspecified"))
      (node (ref "RASPBERRY-TOP1") (pin "27") (pinfunction "27_27") (pintype "unspecified"))
    )
    (net (code "39") (name "GPIO1") (class "Default")
      (node (ref "RASPBERRY-BOTTOM2") (pin "14") (pinfunction "14_14") (pintype "unspecified"))
      (node (ref "RASPBERRY-TOP1") (pin "28") (pinfunction "28_28") (pintype "unspecified"))
    )
    (net (code "40") (name "GPIO4") (class "Default")
      (node (ref "RASPBERRY-BOTTOM2") (pin "33") (pinfunction "33_33") (pintype "unspecified"))
      (node (ref "RASPBERRY-TOP1") (pin "7") (pinfunction "7_7") (pintype "unspecified"))
    )
    (net (code "41") (name "GPIO5") (class "Default")
      (node (ref "RASPBERRY-BOTTOM2") (pin "11") (pinfunction "11_11") (pintype "unspecified"))
      (node (ref "RASPBERRY-TOP1") (pin "29") (pinfunction "29_29") (pintype "unspecified"))
    )
    (net (code "42") (name "GPIO6") (class "Default")
      (node (ref "RASPBERRY-BOTTOM2") (pin "9") (pinfunction "9_9") (pintype "unspecified"))
      (node (ref "RASPBERRY-TOP1") (pin "31") (pinfunction "31_31") (pintype "unspecified"))
    )
    (net (code "43") (name "GPIO7") (class "Default")
      (node (ref "RASPBERRY-BOTTOM2") (pin "16") (pinfunction "16_16") (pintype "unspecified"))
      (node (ref "RASPBERRY-TOP1") (pin "26") (pinfunction "26_26") (pintype "unspecified"))
    )
    (net (code "44") (name "GPIO8") (class "Default")
      (node (ref "RASPBERRY-BOTTOM2") (pin "18") (pinfunction "18_18") (pintype "unspecified"))
      (node (ref "RASPBERRY-TOP1") (pin "24") (pinfunction "24_24") (pintype "unspecified"))
    )
    (net (code "45") (name "GPIO9") (class "Default")
      (node (ref "RASPBERRY-BOTTOM2") (pin "19") (pinfunction "19_19") (pintype "unspecified"))
      (node (ref "RASPBERRY-TOP1") (pin "21") (pinfunction "21_21") (pintype "unspecified"))
    )
    (net (code "46") (name "GPIO10") (class "Default")
      (node (ref "RASPBERRY-BOTTOM2") (pin "21") (pinfunction "21_21") (pintype "unspecified"))
      (node (ref "RASPBERRY-TOP1") (pin "19") (pinfunction "19_19") (pintype "unspecified"))
    )
    (net (code "47") (name "GPIO11") (class "Default")
      (node (ref "RASPBERRY-BOTTOM2") (pin "17") (pinfunction "17_17") (pintype "unspecified"))
      (node (ref "RASPBERRY-TOP1") (pin "23") (pinfunction "23_23") (pintype "unspecified"))
    )
    (net (code "48") (name "GPIO12") (class "Default")
      (node (ref "RASPBERRY-BOTTOM2") (pin "10") (pinfunction "10_10") (pintype "unspecified"))
      (node (ref "RASPBERRY-TOP1") (pin "32") (pinfunction "32_32") (pintype "unspecified"))
    )
    (net (code "49") (name "GPIO13") (class "Default")
      (node (ref "RASPBERRY-BOTTOM2") (pin "7") (pinfunction "7_7") (pintype "unspecified"))
      (node (ref "RASPBERRY-TOP1") (pin "33") (pinfunction "33_33") (pintype "unspecified"))
    )
    (net (code "50") (name "GPIO17") (class "Default")
      (node (ref "RASPBERRY-BOTTOM2") (pin "29") (pinfunction "29_29") (pintype "unspecified"))
      (node (ref "RASPBERRY-TOP1") (pin "11") (pinfunction "11_11") (pintype "unspecified"))
    )
    (net (code "51") (name "GPIO18") (class "Default")
      (node (ref "RASPBERRY-BOTTOM2") (pin "30") (pinfunction "30_30") (pintype "unspecified"))
      (node (ref "RASPBERRY-TOP1") (pin "12") (pinfunction "12_12") (pintype "unspecified"))
    )
    (net (code "52") (name "GPIO22") (class "Default")
      (node (ref "RASPBERRY-BOTTOM2") (pin "25") (pinfunction "25_25") (pintype "unspecified"))
      (node (ref "RASPBERRY-TOP1") (pin "15") (pinfunction "15_15") (pintype "unspecified"))
    )
    (net (code "53") (name "GPIO23") (class "Default")
      (node (ref "RASPBERRY-BOTTOM2") (pin "26") (pinfunction "26_26") (pintype "unspecified"))
      (node (ref "RASPBERRY-TOP1") (pin "16") (pinfunction "16_16") (pintype "unspecified"))
    )
    (net (code "54") (name "GPIO24") (class "Default")
      (node (ref "RASPBERRY-BOTTOM2") (pin "24") (pinfunction "24_24") (pintype "unspecified"))
      (node (ref "RASPBERRY-TOP1") (pin "18") (pinfunction "18_18") (pintype "unspecified"))
    )
    (net (code "55") (name "GPIO25") (class "Default")
      (node (ref "RASPBERRY-BOTTOM2") (pin "20") (pinfunction "20_20") (pintype "unspecified"))
      (node (ref "RASPBERRY-TOP1") (pin "22") (pinfunction "22_22") (pintype "unspecified"))
    )
    (net (code "56") (name "GPIO27") (class "Default")
      (node (ref "RASPBERRY-BOTTOM2") (pin "27") (pinfunction "27_27") (pintype "unspecified"))
      (node (ref "RASPBERRY-TOP1") (pin "13") (pinfunction "13_13") (pintype "unspecified"))
    )
    (net (code "57") (name "I2C_SCL") (class "Default")
      (node (ref "DAC1") (pin "5") (pinfunction "SCL_5") (pintype "unspecified"))
      (node (ref "DAC2") (pin "5") (pinfunction "SCL_5") (pintype "unspecified"))
      (node (ref "FPC1") (pin "19") (pinfunction "19_19") (pintype "unspecified"))
      (node (ref "R16") (pin "1") (pinfunction "1_1") (pintype "unspecified"))
      (node (ref "RASPBERRY-BOTTOM2") (pin "35") (pinfunction "35_35") (pintype "unspecified"))
      (node (ref "RASPBERRY-TOP1") (pin "5") (pinfunction "5_5") (pintype "unspecified"))
      (node (ref "U10") (pin "37") (pinfunction "IOT_45a_G1_37") (pintype "unspecified"))
    )
    (net (code "58") (name "I2C_SDA") (class "Default")
      (node (ref "DAC1") (pin "4") (pinfunction "SDA_4") (pintype "bidirectional"))
      (node (ref "DAC2") (pin "4") (pinfunction "SDA_4") (pintype "bidirectional"))
      (node (ref "FPC1") (pin "20") (pinfunction "20_20") (pintype "unspecified"))
      (node (ref "R17") (pin "1") (pinfunction "1_1") (pintype "unspecified"))
      (node (ref "RASPBERRY-BOTTOM2") (pin "37") (pinfunction "37_37") (pintype "unspecified"))
      (node (ref "RASPBERRY-TOP1") (pin "3") (pinfunction "3_3") (pintype "unspecified"))
      (node (ref "U10") (pin "38") (pinfunction "IOT_50b_38") (pintype "unspecified"))
    )
    (net (code "59") (name "Net-(CLK1-VDD)") (class "Default")
      (node (ref "CLK1") (pin "4") (pinfunction "VDD_4") (pintype "unspecified"))
      (node (ref "RN2") (pin "6") (pinfunction "6_6") (pintype "unspecified"))
      (node (ref "RN2") (pin "7") (pinfunction "7_7") (pintype "unspecified"))
      (node (ref "RN2") (pin "8") (pinfunction "8_8") (pintype "unspecified"))
    )
    (net (code "60") (name "Net-(D1-A)") (class "Default")
      (node (ref "C1") (pin "1") (pinfunction "1_1") (pintype "input"))
      (node (ref "D1") (pin "2") (pinfunction "A_2") (pintype "unspecified"))
      (node (ref "U1") (pin "1") (pinfunction "1_1") (pintype "unspecified"))
    )
    (net (code "61") (name "Net-(DAC1-A0)") (class "Default")
      (node (ref "DAC1") (pin "6") (pinfunction "A0_6") (pintype "unspecified"))
      (node (ref "R20") (pin "2") (pinfunction "2_2") (pintype "unspecified"))
    )
    (net (code "62") (name "Net-(DAC2-A0)") (class "Default")
      (node (ref "DAC2") (pin "6") (pinfunction "A0_6") (pintype "unspecified"))
      (node (ref "R21") (pin "2") (pinfunction "2_2") (pintype "unspecified"))
    )
    (net (code "63") (name "Net-(FLASH1-CS#)") (class "Default")
      (node (ref "FLASH1") (pin "1") (pinfunction "CS#_1") (pintype "unspecified"))
      (node (ref "R10") (pin "1") (pinfunction "1_1") (pintype "unspecified"))
      (node (ref "R9") (pin "2") (pinfunction "2_2") (pintype "unspecified"))
    )
    (net (code "64") (name "Net-(FLASH1-HOLD#orRESET#(IO3))") (class "Default")
      (node (ref "FLASH1") (pin "7") (pinfunction "HOLD#orRESET#(IO3)_7") (pintype "unspecified"))
      (node (ref "R7") (pin "1") (pinfunction "1_1") (pintype "unspecified"))
    )
    (net (code "65") (name "Net-(FLASH1-WP#(IO2))") (class "Default")
      (node (ref "FLASH1") (pin "3") (pinfunction "WP#(IO2)_3") (pintype "unspecified"))
      (node (ref "R11") (pin "1") (pinfunction "1_1") (pintype "unspecified"))
    )
    (net (code "66") (name "Net-(FPC1-Pad25)") (class "Default")
      (node (ref "FPC1") (pin "25") (pinfunction "25_25") (pintype "unspecified"))
      (node (ref "RN4") (pin "1") (pinfunction "1_1") (pintype "unspecified"))
    )
    (net (code "67") (name "Net-(FPC1-Pad26)") (class "Default")
      (node (ref "FPC1") (pin "26") (pinfunction "26_26") (pintype "unspecified"))
      (node (ref "RN4") (pin "2") (pinfunction "2_2") (pintype "unspecified"))
    )
    (net (code "68") (name "Net-(FPC1-Pad27)") (class "Default")
      (node (ref "FPC1") (pin "27") (pinfunction "27_27") (pintype "unspecified"))
      (node (ref "RN4") (pin "3") (pinfunction "3_3") (pintype "unspecified"))
    )
    (net (code "69") (name "Net-(FPC1-Pad28)") (class "Default")
      (node (ref "FPC1") (pin "28") (pinfunction "28_28") (pintype "unspecified"))
      (node (ref "RN4") (pin "4") (pinfunction "4_4") (pintype "unspecified"))
    )
    (net (code "70") (name "Net-(FPC1-Pad29)") (class "Default")
      (node (ref "FPC1") (pin "29") (pinfunction "29_29") (pintype "unspecified"))
      (node (ref "RN5") (pin "1") (pinfunction "1_1") (pintype "unspecified"))
    )
    (net (code "71") (name "Net-(FPC1-Pad30)") (class "Default")
      (node (ref "FPC1") (pin "30") (pinfunction "30_30") (pintype "unspecified"))
      (node (ref "RN5") (pin "2") (pinfunction "2_2") (pintype "unspecified"))
    )
    (net (code "72") (name "Net-(FPC1-Pad31)") (class "Default")
      (node (ref "FPC1") (pin "31") (pinfunction "31_31") (pintype "unspecified"))
      (node (ref "RN5") (pin "3") (pinfunction "3_3") (pintype "unspecified"))
    )
    (net (code "73") (name "Net-(FPC1-Pad32)") (class "Default")
      (node (ref "FPC1") (pin "32") (pinfunction "32_32") (pintype "unspecified"))
      (node (ref "RN5") (pin "4") (pinfunction "4_4") (pintype "unspecified"))
    )
    (net (code "74") (name "Net-(FPC1-Pad33)") (class "Default")
      (node (ref "FPC1") (pin "33") (pinfunction "33_33") (pintype "unspecified"))
      (node (ref "RN6") (pin "1") (pinfunction "1_1") (pintype "unspecified"))
    )
    (net (code "75") (name "Net-(FPC1-Pad34)") (class "Default")
      (node (ref "FPC1") (pin "34") (pinfunction "34_34") (pintype "unspecified"))
      (node (ref "RN6") (pin "2") (pinfunction "2_2") (pintype "unspecified"))
    )
    (net (code "76") (name "Net-(FPC1-Pad35)") (class "Default")
      (node (ref "FPC1") (pin "35") (pinfunction "35_35") (pintype "unspecified"))
      (node (ref "RN6") (pin "3") (pinfunction "3_3") (pintype "unspecified"))
    )
    (net (code "77") (name "Net-(FPC1-Pad36)") (class "Default")
      (node (ref "FPC1") (pin "36") (pinfunction "36_36") (pintype "unspecified"))
      (node (ref "RN6") (pin "4") (pinfunction "4_4") (pintype "unspecified"))
    )
    (net (code "78") (name "Net-(FPC1-Pad42)") (class "Default")
      (node (ref "FPC1") (pin "42") (pinfunction "42_42") (pintype "unspecified"))
      (node (ref "RN1") (pin "1") (pinfunction "1_1") (pintype "unspecified"))
    )
    (net (code "79") (name "Net-(FPC1-Pad43)") (class "Default")
      (node (ref "FPC1") (pin "43") (pinfunction "43_43") (pintype "unspecified"))
      (node (ref "RN1") (pin "2") (pinfunction "2_2") (pintype "unspecified"))
    )
    (net (code "80") (name "Net-(FPC1-Pad44)") (class "Default")
      (node (ref "FPC1") (pin "44") (pinfunction "44_44") (pintype "unspecified"))
      (node (ref "RN1") (pin "3") (pinfunction "3_3") (pintype "unspecified"))
    )
    (net (code "81") (name "Net-(FPC1-Pad45)") (class "Default")
      (node (ref "FPC1") (pin "45") (pinfunction "45_45") (pintype "unspecified"))
      (node (ref "RN1") (pin "4") (pinfunction "4_4") (pintype "unspecified"))
    )
    (net (code "82") (name "Net-(FPC1-Pad46)") (class "Default")
      (node (ref "FPC1") (pin "46") (pinfunction "46_46") (pintype "unspecified"))
      (node (ref "RN3") (pin "1") (pinfunction "1_1") (pintype "unspecified"))
    )
    (net (code "83") (name "Net-(FPC1-Pad47)") (class "Default")
      (node (ref "FPC1") (pin "47") (pinfunction "47_47") (pintype "unspecified"))
      (node (ref "RN3") (pin "2") (pinfunction "2_2") (pintype "unspecified"))
    )
    (net (code "84") (name "Net-(FPC1-Pad48)") (class "Default")
      (node (ref "FPC1") (pin "48") (pinfunction "48_48") (pintype "unspecified"))
      (node (ref "RN3") (pin "3") (pinfunction "3_3") (pintype "unspecified"))
    )
    (net (code "85") (name "Net-(FPC1-Pad49)") (class "Default")
      (node (ref "FPC1") (pin "49") (pinfunction "49_49") (pintype "unspecified"))
      (node (ref "RN3") (pin "4") (pinfunction "4_4") (pintype "unspecified"))
    )
    (net (code "86") (name "Net-(LED2-Pad1)") (class "Default")
      (node (ref "LED2") (pin "1") (pinfunction "1_1") (pintype "unspecified"))
      (node (ref "R5") (pin "1") (pinfunction "1_1") (pintype "input"))
    )
    (net (code "87") (name "Net-(RN2-Pad1)") (class "Default")
      (node (ref "RN2") (pin "1") (pinfunction "1_1") (pintype "unspecified"))
      (node (ref "RN2") (pin "2") (pinfunction "2_2") (pintype "unspecified"))
      (node (ref "RN2") (pin "3") (pinfunction "3_3") (pintype "unspecified"))
      (node (ref "RN2") (pin "4") (pinfunction "4_4") (pintype "unspecified"))
    )
    (net (code "88") (name "PWM-RGB0") (class "Default")
      (node (ref "FPC1") (pin "38") (pinfunction "38_38") (pintype "unspecified"))
      (node (ref "U10") (pin "39") (pinfunction "RGB0_39") (pintype "unspecified"))
    )
    (net (code "89") (name "PWM-RGB1") (class "Default")
      (node (ref "FPC1") (pin "39") (pinfunction "39_39") (pintype "unspecified"))
      (node (ref "U10") (pin "40") (pinfunction "RGB1_40") (pintype "unspecified"))
    )
    (net (code "90") (name "PWM-RGB2") (class "Default")
      (node (ref "FPC1") (pin "40") (pinfunction "40_40") (pintype "unspecified"))
      (node (ref "U10") (pin "41") (pinfunction "RGB2_41") (pintype "unspecified"))
    )
    (net (code "91") (name "PWR1v2") (class "Default")
      (node (ref "C8") (pin "1") (pinfunction "1_1") (pintype "input"))
      (node (ref "C9") (pin "2") (pinfunction "2_2") (pintype "input"))
      (node (ref "R1") (pin "1") (pinfunction "1_1") (pintype "unspecified"))
      (node (ref "R2") (pin "1") (pinfunction "1_1") (pintype "unspecified"))
      (node (ref "U3") (pin "4") (pinfunction "TAB_4") (pintype "unspecified"))
    )
    (net (code "92") (name "PWR3v3") (class "Default")
      (node (ref "C6") (pin "1") (pinfunction "1_1") (pintype "input"))
      (node (ref "C7") (pin "2") (pinfunction "2_2") (pintype "input"))
      (node (ref "D2") (pin "2") (pinfunction "A_2") (pintype "unspecified"))
      (node (ref "R3") (pin "1") (pinfunction "1_1") (pintype "unspecified"))
      (node (ref "U2") (pin "4") (pinfunction "TAB_4") (pintype "unspecified"))
    )
    (net (code "93") (name "PWR5v") (class "Default")
      (node (ref "C2") (pin "1") (pinfunction "1_1") (pintype "input"))
      (node (ref "C3") (pin "2") (pinfunction "2_2") (pintype "input"))
      (node (ref "C4") (pin "2") (pinfunction "2_2") (pintype "input"))
      (node (ref "C5") (pin "2") (pinfunction "2_2") (pintype "input"))
      (node (ref "D1") (pin "1") (pinfunction "C_1") (pintype "unspecified"))
      (node (ref "R5") (pin "2") (pinfunction "2_2") (pintype "input"))
      (node (ref "U2") (pin "3") (pinfunction "VIN_3") (pintype "unspecified"))
      (node (ref "U3") (pin "3") (pinfunction "VIN_3") (pintype "unspecified"))
      (node (ref "VLOGIC1") (pin "19") (pinfunction "VCCB_19") (pintype "unspecified"))
    )
    (net (code "94") (name "SCLK-ICE") (class "Default")
      (node (ref "FLASH1") (pin "6") (pinfunction "CLK_6") (pintype "unspecified"))
      (node (ref "R8") (pin "1") (pinfunction "1_1") (pintype "unspecified"))
      (node (ref "RASPBERRY-BOTTOM2") (pin "6") (pinfunction "6_6") (pintype "unspecified"))
      (node (ref "RASPBERRY-TOP1") (pin "36") (pinfunction "36_36") (pintype "unspecified"))
      (node (ref "U10") (pin "15") (pinfunction "IOB_34a_SPI_SCK_15") (pintype "unspecified"))
    )
    (net (code "95") (name "SDI") (class "Default")
      (node (ref "FLASH1") (pin "5") (pinfunction "DI(IO0)_5") (pintype "unspecified"))
      (node (ref "R13") (pin "1") (pinfunction "1_1") (pintype "unspecified"))
      (node (ref "RASPBERRY-BOTTOM2") (pin "4") (pinfunction "4_4") (pintype "unspecified"))
      (node (ref "RASPBERRY-TOP1") (pin "38") (pinfunction "38_38") (pintype "unspecified"))
    )
    (net (code "96") (name "SDI-ICE") (class "Default")
      (node (ref "R12") (pin "2") (pinfunction "2_2") (pintype "unspecified"))
      (node (ref "U10") (pin "17") (pinfunction "IOB_33b_SPI_SI_17") (pintype "unspecified"))
    )
    (net (code "97") (name "SDO") (class "Default")
      (node (ref "FLASH1") (pin "2") (pinfunction "DO(IO1)_2") (pintype "unspecified"))
      (node (ref "R12") (pin "1") (pinfunction "1_1") (pintype "unspecified"))
      (node (ref "RASPBERRY-BOTTOM2") (pin "5") (pinfunction "5_5") (pintype "unspecified"))
      (node (ref "RASPBERRY-TOP1") (pin "35") (pinfunction "35_35") (pintype "unspecified"))
    )
    (net (code "98") (name "SDO-ICE") (class "Default")
      (node (ref "R13") (pin "2") (pinfunction "2_2") (pintype "unspecified"))
      (node (ref "U10") (pin "14") (pinfunction "IOB_32a_SPI_SO_14") (pintype "unspecified"))
    )
    (net (code "99") (name "SHDN") (class "Default")
      (node (ref "ADC1") (pin "10") (pinfunction "SHDN#_10") (pintype "unspecified"))
      (node (ref "R14") (pin "2") (pinfunction "2_2") (pintype "unspecified"))
      (node (ref "U10") (pin "43") (pinfunction "IOT_49a_43") (pintype "unspecified"))
    )
    (net (code "100") (name "UART-RXD") (class "Default")
      (node (ref "FPC1") (pin "22") (pinfunction "22_22") (pintype "unspecified"))
      (node (ref "R18") (pin "1") (pinfunction "1_1") (pintype "unspecified"))
      (node (ref "RASPBERRY-BOTTOM2") (pin "34") (pinfunction "34_34") (pintype "unspecified"))
      (node (ref "RASPBERRY-TOP1") (pin "8") (pinfunction "8_8") (pintype "unspecified"))
      (node (ref "U10") (pin "4") (pinfunction "IOB_8a_4") (pintype "unspecified"))
    )
    (net (code "101") (name "UART-TXD") (class "Default")
      (node (ref "FPC1") (pin "23") (pinfunction "23_23") (pintype "unspecified"))
      (node (ref "R19") (pin "1") (pinfunction "1_1") (pintype "unspecified"))
      (node (ref "RASPBERRY-BOTTOM2") (pin "32") (pinfunction "32_32") (pintype "unspecified"))
      (node (ref "RASPBERRY-TOP1") (pin "10") (pinfunction "10_10") (pintype "unspecified"))
      (node (ref "U10") (pin "6") (pinfunction "IOB_13b_6") (pintype "unspecified"))
    )
    (net (code "102") (name "Vcc") (class "Default")
      (node (ref "C16") (pin "2") (pinfunction "2_2") (pintype "input"))
      (node (ref "C17") (pin "2") (pinfunction "2_2") (pintype "input"))
      (node (ref "C18") (pin "2") (pinfunction "2_2") (pintype "input"))
      (node (ref "C19") (pin "2") (pinfunction "2_2") (pintype "input"))
      (node (ref "C20") (pin "2") (pinfunction "2_2") (pintype "input"))
      (node (ref "C21") (pin "1") (pinfunction "1_1") (pintype "input"))
      (node (ref "R2") (pin "2") (pinfunction "2_2") (pintype "unspecified"))
      (node (ref "U10") (pin "30") (pinfunction "VCC_30") (pintype "unspecified"))
      (node (ref "U10") (pin "5") (pinfunction "VCC_5") (pintype "unspecified"))
    )
    (net (code "103") (name "Vcc-5v") (class "Default")
      (node (ref "RASPBERRY-BOTTOM2") (pin "38") (pinfunction "38_38") (pintype "unspecified"))
      (node (ref "RASPBERRY-TOP1") (pin "4") (pinfunction "4_4") (pintype "unspecified"))
      (node (ref "U1") (pin "2") (pinfunction "2_2") (pintype "unspecified"))
    )
    (net (code "104") (name "Vccpll") (class "Default")
      (node (ref "C10") (pin "1") (pinfunction "1_1") (pintype "input"))
      (node (ref "C11") (pin "2") (pinfunction "2_2") (pintype "input"))
      (node (ref "C12") (pin "2") (pinfunction "2_2") (pintype "input"))
      (node (ref "C13") (pin "2") (pinfunction "2_2") (pintype "input"))
      (node (ref "C14") (pin "2") (pinfunction "2_2") (pintype "input"))
      (node (ref "C15") (pin "2") (pinfunction "2_2") (pintype "input"))
      (node (ref "R1") (pin "2") (pinfunction "2_2") (pintype "unspecified"))
      (node (ref "U10") (pin "29") (pinfunction "VCCPLL_29") (pintype "unspecified"))
    )
    (net (code "105") (name "Vlogic-00") (class "Default")
      (node (ref "RN3") (pin "5") (pinfunction "5_5") (pintype "unspecified"))
      (node (ref "VLOGIC1") (pin "20") (pinfunction "B1_20") (pintype "unspecified"))
    )
    (net (code "106") (name "Vlogic-00in{slash}out") (class "Default")
      (node (ref "U10") (pin "36") (pinfunction "IOT_48b_36") (pintype "unspecified"))
      (node (ref "VLOGIC1") (pin "1") (pinfunction "A1_1") (pintype "unspecified"))
    )
    (net (code "107") (name "Vlogic-01") (class "Default")
      (node (ref "RN3") (pin "6") (pinfunction "6_6") (pintype "unspecified"))
      (node (ref "VLOGIC1") (pin "18") (pinfunction "B2_18") (pintype "unspecified"))
    )
    (net (code "108") (name "Vlogic-01in{slash}out") (class "Default")
      (node (ref "U10") (pin "34") (pinfunction "IOT_44b_34") (pintype "unspecified"))
      (node (ref "VLOGIC1") (pin "3") (pinfunction "A2_3") (pintype "unspecified"))
    )
    (net (code "109") (name "Vlogic-02") (class "Default")
      (node (ref "RN3") (pin "7") (pinfunction "7_7") (pintype "unspecified"))
      (node (ref "VLOGIC1") (pin "17") (pinfunction "B3_17") (pintype "unspecified"))
    )
    (net (code "110") (name "Vlogic-02in{slash}out") (class "Default")
      (node (ref "U10") (pin "32") (pinfunction "IOT_43a_32") (pintype "unspecified"))
      (node (ref "VLOGIC1") (pin "4") (pinfunction "A3_4") (pintype "unspecified"))
    )
    (net (code "111") (name "Vlogic-03") (class "Default")
      (node (ref "RN3") (pin "8") (pinfunction "8_8") (pintype "unspecified"))
      (node (ref "VLOGIC1") (pin "16") (pinfunction "B4_16") (pintype "unspecified"))
    )
    (net (code "112") (name "Vlogic-03in{slash}out") (class "Default")
      (node (ref "U10") (pin "31") (pinfunction "IOT_42b_31") (pintype "unspecified"))
      (node (ref "VLOGIC1") (pin "5") (pinfunction "A4_5") (pintype "unspecified"))
    )
    (net (code "113") (name "Vlogic-04") (class "Default")
      (node (ref "RN1") (pin "5") (pinfunction "5_5") (pintype "unspecified"))
      (node (ref "VLOGIC1") (pin "15") (pinfunction "B5_15") (pintype "unspecified"))
    )
    (net (code "114") (name "Vlogic-04in{slash}out") (class "Default")
      (node (ref "U10") (pin "28") (pinfunction "IOT_41a_28") (pintype "unspecified"))
      (node (ref "VLOGIC1") (pin "6") (pinfunction "A5_6") (pintype "unspecified"))
    )
    (net (code "115") (name "Vlogic-05") (class "Default")
      (node (ref "RN1") (pin "6") (pinfunction "6_6") (pintype "unspecified"))
      (node (ref "VLOGIC1") (pin "14") (pinfunction "B6_14") (pintype "unspecified"))
    )
    (net (code "116") (name "Vlogic-05in{slash}out") (class "Default")
      (node (ref "U10") (pin "27") (pinfunction "IOT_38b_27") (pintype "unspecified"))
      (node (ref "VLOGIC1") (pin "7") (pinfunction "A6_7") (pintype "unspecified"))
    )
    (net (code "117") (name "Vlogic-06") (class "Default")
      (node (ref "RN1") (pin "7") (pinfunction "7_7") (pintype "unspecified"))
      (node (ref "VLOGIC1") (pin "13") (pinfunction "B7_13") (pintype "unspecified"))
    )
    (net (code "118") (name "Vlogic-06in{slash}out") (class "Default")
      (node (ref "U10") (pin "26") (pinfunction "IOT_39a_26") (pintype "unspecified"))
      (node (ref "VLOGIC1") (pin "8") (pinfunction "A7_8") (pintype "unspecified"))
    )
    (net (code "119") (name "Vlogic-07") (class "Default")
      (node (ref "RN1") (pin "8") (pinfunction "8_8") (pintype "unspecified"))
      (node (ref "VLOGIC1") (pin "12") (pinfunction "B8_12") (pintype "unspecified"))
    )
    (net (code "120") (name "Vlogic-07in{slash}out") (class "Default")
      (node (ref "U10") (pin "25") (pinfunction "IOT_36b_25") (pintype "unspecified"))
      (node (ref "VLOGIC1") (pin "9") (pinfunction "A8_9") (pintype "unspecified"))
    )
    (net (code "121") (name "Vlogic_OE") (class "Default")
      (node (ref "R15") (pin "1") (pinfunction "1_1") (pintype "unspecified"))
      (node (ref "U10") (pin "42") (pinfunction "IOT_51a_42") (pintype "unspecified"))
      (node (ref "VLOGIC1") (pin "10") (pinfunction "OE_10") (pintype "unspecified"))
    )
    (net (code "122") (name "Vpp_2v5") (class "Default")
      (node (ref "C22") (pin "1") (pinfunction "1_1") (pintype "input"))
      (node (ref "C23") (pin "2") (pinfunction "2_2") (pintype "input"))
      (node (ref "C24") (pin "2") (pinfunction "2_2") (pintype "input"))
      (node (ref "C25") (pin "2") (pinfunction "2_2") (pintype "input"))
      (node (ref "C26") (pin "2") (pinfunction "2_2") (pintype "input"))
      (node (ref "C27") (pin "2") (pinfunction "2_2") (pintype "input"))
      (node (ref "D2") (pin "1") (pinfunction "C_1") (pintype "unspecified"))
      (node (ref "U10") (pin "24") (pinfunction "VPP_2V5_24") (pintype "unspecified"))
    )
    (net (code "123") (name "unconnected-(U2-VOUT(TAB)-Pad2)") (class "Default")
      (node (ref "U2") (pin "2") (pinfunction "VOUT(TAB)_2") (pintype "unspecified+no_connect"))
    )
    (net (code "124") (name "unconnected-(U3-VOUT(TAB)-Pad2)") (class "Default")
      (node (ref "U3") (pin "2") (pinfunction "VOUT(TAB)_2") (pintype "unspecified+no_connect"))
    )
  )
)
